# system-controller.net
KiCad netlist of a schematic drawn in EAGLE
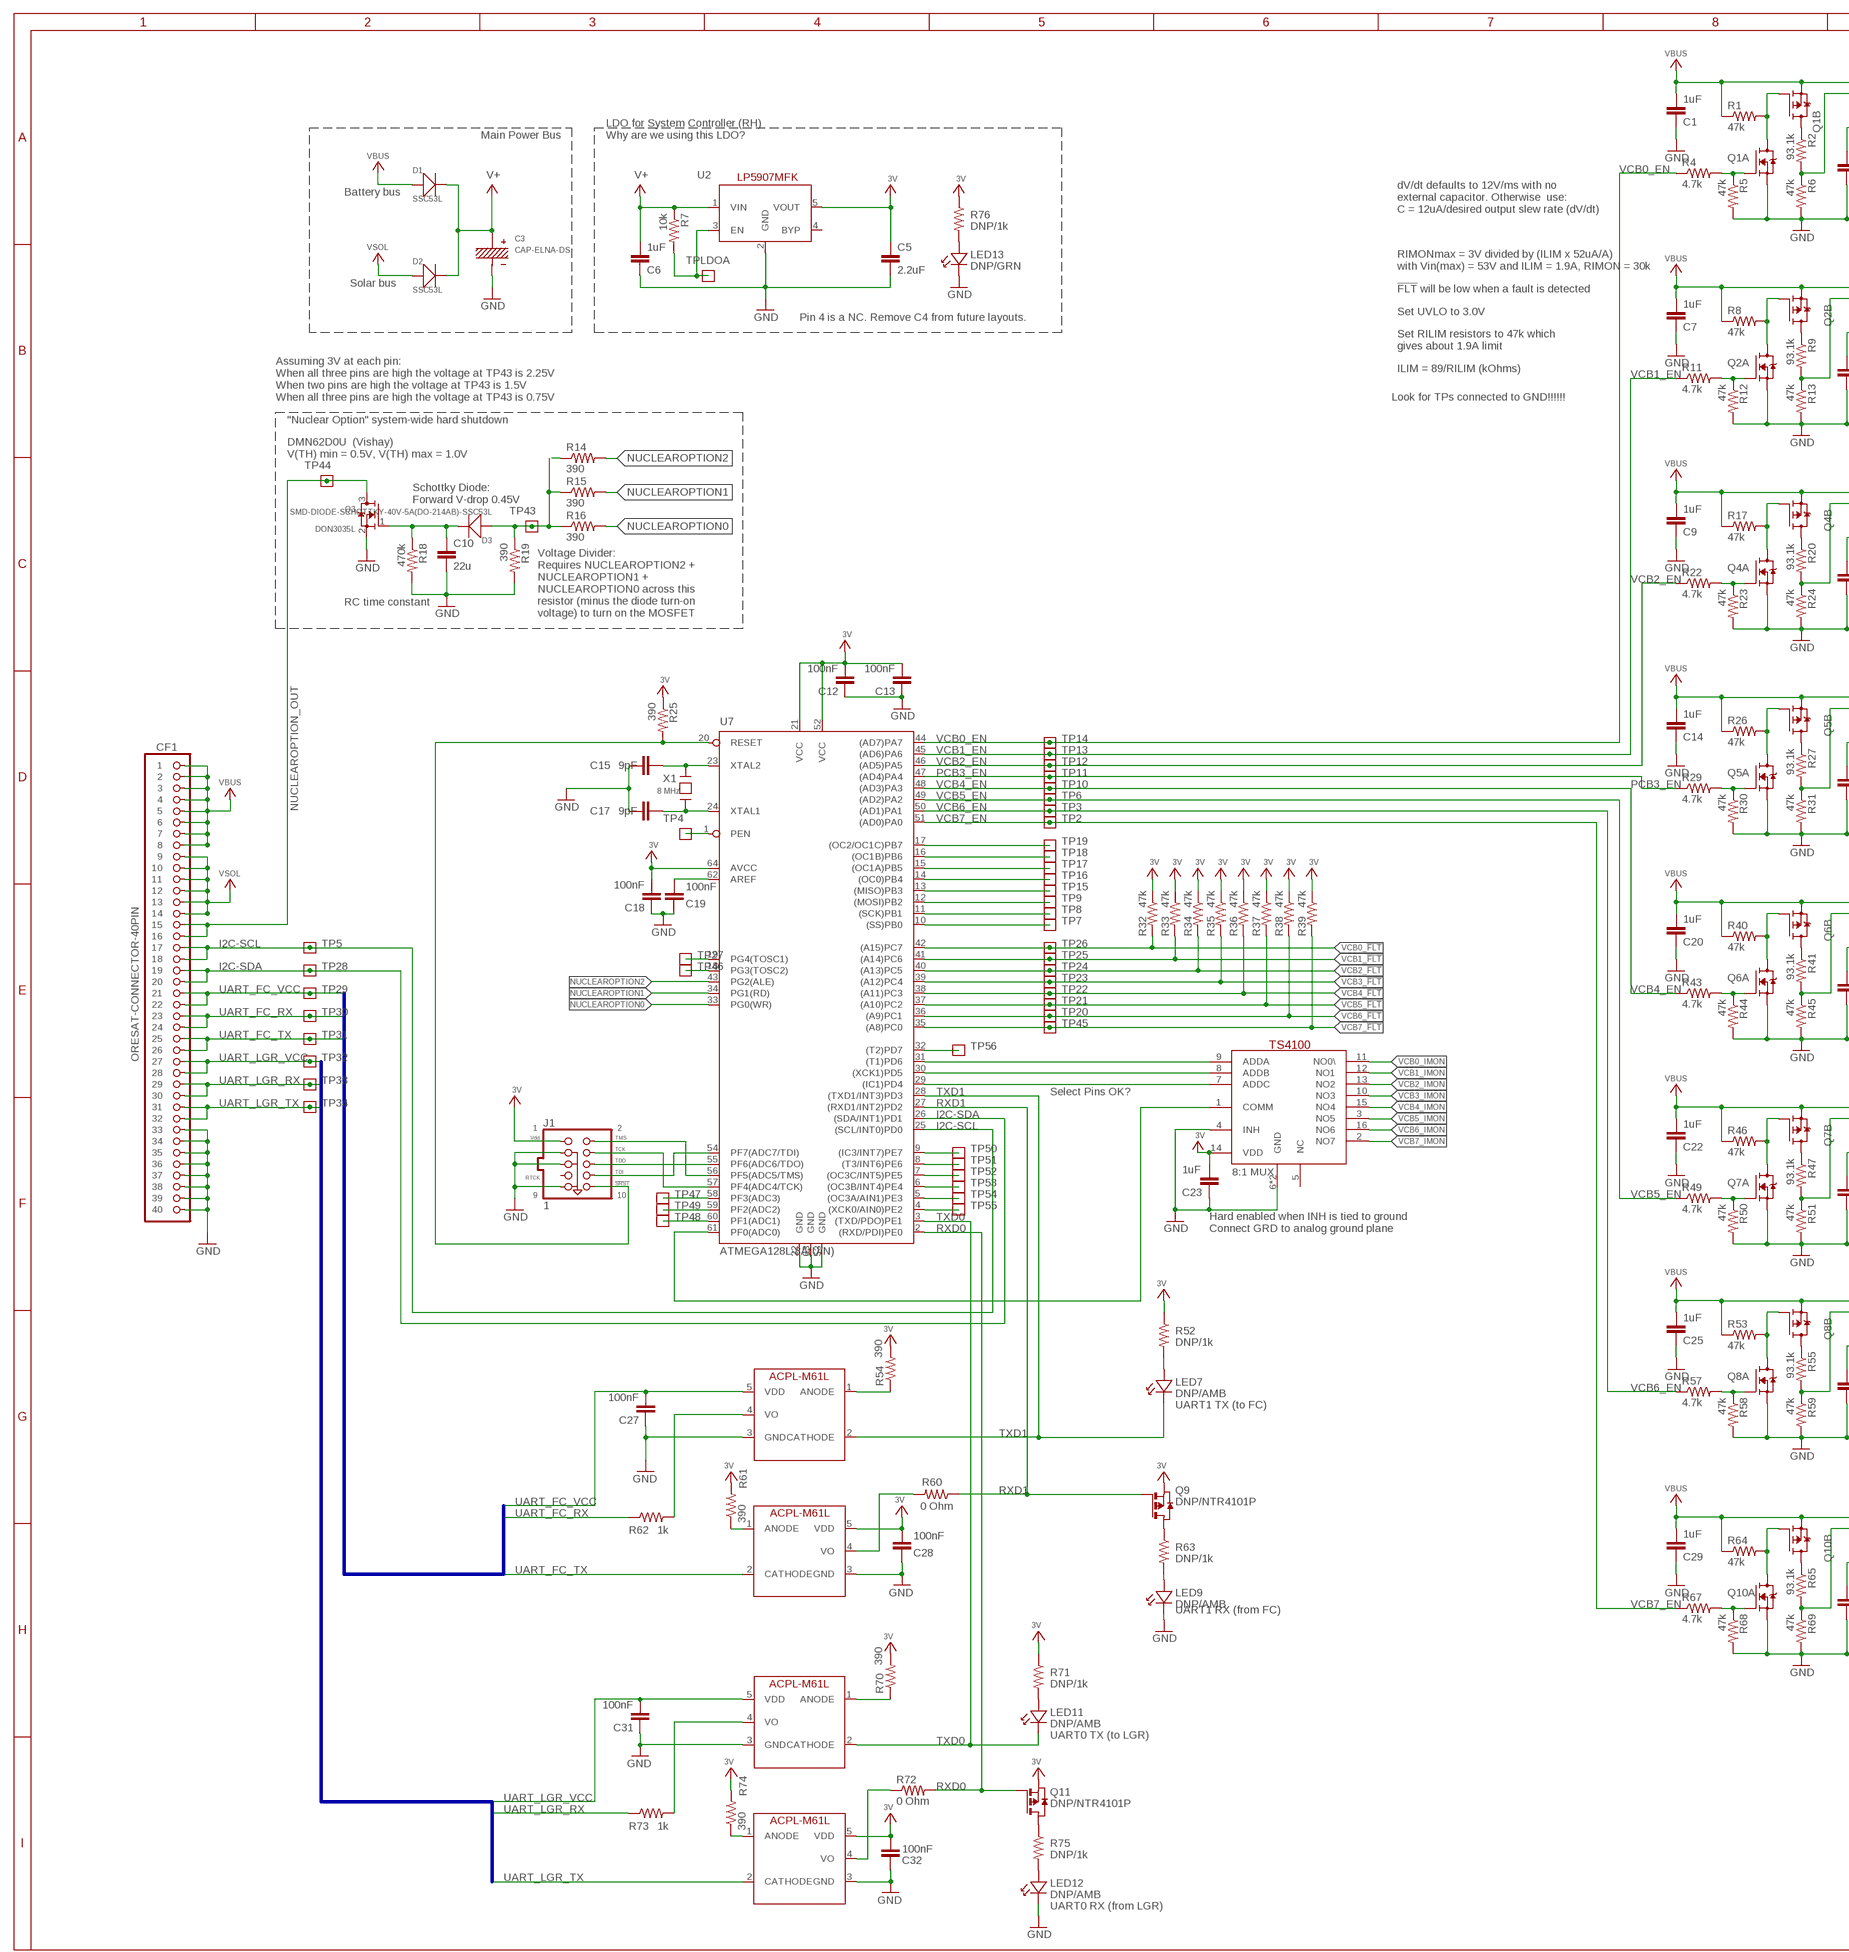
[diagram p0: schematic, sheet 1, part 1 of 2]
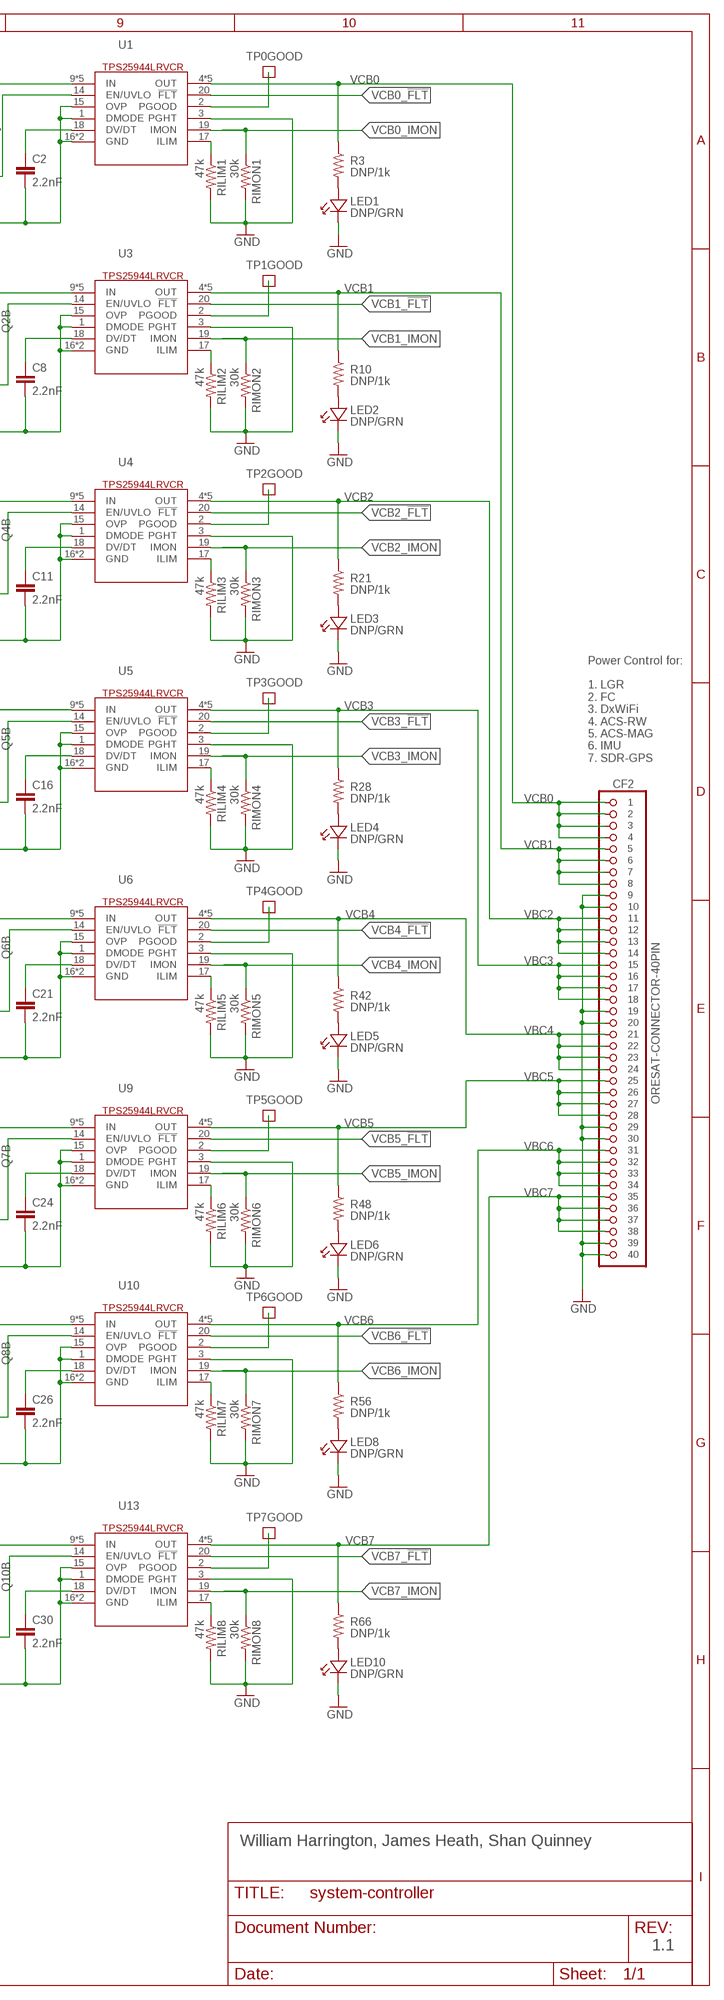
[diagram p1: schematic, sheet 1, part 2 of 2]

(export (version "E")
  (design (tool "Eeschema 10.0.6"))
  (components
    (comp (ref "C1")
      (value "1uF")
      (footprint "eagle-import:.0603-B-NOSILK")
      (fields (field (name "MPN") "CL10B105KP8NNNC"))
      (libsource (lib "eagle-import") (part "C-EU0603-B-NOSILK"))
    )
    (comp (ref "C2")
      (value "2.2nF")
      (footprint "eagle-import:.0603-B-NOSILK")
      (fields (field (name "MPN") "CL10C222GA8NNNC"))
      (libsource (lib "eagle-import") (part "C-EU0603-B-NOSILK"))
    )
    (comp (ref "C3")
      (value "CAP-ELNA-DS")
      (footprint "eagle-import:CAP-ELNA-DS-SERIES")
      (fields (field (name "MPN") "DSK-3R3H224U-HL"))
      (libsource (lib "eagle-import") (part "CAP-ELNA-DS"))
    )
    (comp (ref "C5")
      (value "2.2uF")
      (footprint "eagle-import:.0603-B-NOSILK")
      (fields (field (name "MPN") "CL10A225KQ8NNNC"))
      (libsource (lib "eagle-import") (part "C-EU0603-B-NOSILK"))
    )
    (comp (ref "C6")
      (value "1uF")
      (footprint "eagle-import:.0603-B-NOSILK")
      (fields (field (name "MPN") "CL10B105KP8NNNC"))
      (libsource (lib "eagle-import") (part "C-EU0603-B-NOSILK"))
    )
    (comp (ref "C7")
      (value "1uF")
      (footprint "eagle-import:.0603-B-NOSILK")
      (fields (field (name "MPN") "CL10B105KP8NNNC"))
      (libsource (lib "eagle-import") (part "C-EU0603-B-NOSILK"))
    )
    (comp (ref "C8")
      (value "2.2nF")
      (footprint "eagle-import:.0603-B-NOSILK")
      (fields (field (name "MPN") "CL10C222GA8NNNC"))
      (libsource (lib "eagle-import") (part "C-EU0603-B-NOSILK"))
    )
    (comp (ref "C9")
      (value "1uF")
      (footprint "eagle-import:.0603-B-NOSILK")
      (fields (field (name "MPN") "CL10B105KP8NNNC"))
      (libsource (lib "eagle-import") (part "C-EU0603-B-NOSILK"))
    )
    (comp (ref "C10")
      (value "22u")
      (footprint "eagle-import:.0603-B-NOSILK")
      (fields (field (name "MPN") "C0603C103J5RACTU"))
      (libsource (lib "eagle-import") (part "C-EU0603-B-NOSILK"))
    )
    (comp (ref "C11")
      (value "2.2nF")
      (footprint "eagle-import:.0603-B-NOSILK")
      (fields (field (name "MPN") "CL10C222GA8NNNC"))
      (libsource (lib "eagle-import") (part "C-EU0603-B-NOSILK"))
    )
    (comp (ref "C12")
      (value "100nF")
      (footprint "eagle-import:.0603-B-NOSILK")
      (fields (field (name "MPN") "C0603C104J4RACTU"))
      (libsource (lib "eagle-import") (part "C-EU0603-B-NOSILK"))
    )
    (comp (ref "C13")
      (value "100nF")
      (footprint "eagle-import:.0603-B-NOSILK")
      (fields (field (name "MPN") "C0603C104J4RACTU"))
      (libsource (lib "eagle-import") (part "C-EU0603-B-NOSILK"))
    )
    (comp (ref "C14")
      (value "1uF")
      (footprint "eagle-import:.0603-B-NOSILK")
      (fields (field (name "MPN") "CL10B105KP8NNNC"))
      (libsource (lib "eagle-import") (part "C-EU0603-B-NOSILK"))
    )
    (comp (ref "C15")
      (value "9pF")
      (footprint "eagle-import:.0603-B-NOSILK")
      (fields (field (name "MPN") "CBR02C909B5GAC"))
      (libsource (lib "eagle-import") (part "C-EU0603-B-NOSILK"))
    )
    (comp (ref "C16")
      (value "2.2nF")
      (footprint "eagle-import:.0603-B-NOSILK")
      (fields (field (name "MPN") "CL10C222GA8NNNC"))
      (libsource (lib "eagle-import") (part "C-EU0603-B-NOSILK"))
    )
    (comp (ref "C17")
      (value "9pF")
      (footprint "eagle-import:.0603-B-NOSILK")
      (fields (field (name "MPN") "CBR02C909B5GAC"))
      (libsource (lib "eagle-import") (part "C-EU0603-B-NOSILK"))
    )
    (comp (ref "C18")
      (value "100nF")
      (footprint "eagle-import:.0603-B-NOSILK")
      (fields (field (name "MPN") "C0603C104J4RACTU"))
      (libsource (lib "eagle-import") (part "C-EU0603-B-NOSILK"))
    )
    (comp (ref "C19")
      (value "100nF")
      (footprint "eagle-import:.0603-B-NOSILK")
      (fields (field (name "MPN") "C0603C104J4RACTU"))
      (libsource (lib "eagle-import") (part "C-EU0603-B-NOSILK"))
    )
    (comp (ref "C20")
      (value "1uF")
      (footprint "eagle-import:.0603-B-NOSILK")
      (fields (field (name "MPN") "CL10B105KP8NNNC"))
      (libsource (lib "eagle-import") (part "C-EU0603-B-NOSILK"))
    )
    (comp (ref "C21")
      (value "2.2nF")
      (footprint "eagle-import:.0603-B-NOSILK")
      (fields (field (name "MPN") "CL10C222GA8NNNC"))
      (libsource (lib "eagle-import") (part "C-EU0603-B-NOSILK"))
    )
    (comp (ref "C22")
      (value "1uF")
      (footprint "eagle-import:.0603-B-NOSILK")
      (fields (field (name "MPN") "CL10B105KP8NNNC"))
      (libsource (lib "eagle-import") (part "C-EU0603-B-NOSILK"))
    )
    (comp (ref "C23")
      (value "1uF")
      (footprint "eagle-import:.0603-B-NOSILK")
      (fields (field (name "MPN") "CL10B105KP8NNNC"))
      (libsource (lib "eagle-import") (part "C-EU0603-B-NOSILK"))
    )
    (comp (ref "C24")
      (value "2.2nF")
      (footprint "eagle-import:.0603-B-NOSILK")
      (fields (field (name "MPN") "CL10C222GA8NNNC"))
      (libsource (lib "eagle-import") (part "C-EU0603-B-NOSILK"))
    )
    (comp (ref "C25")
      (value "1uF")
      (footprint "eagle-import:.0603-B-NOSILK")
      (fields (field (name "MPN") "CL10B105KP8NNNC"))
      (libsource (lib "eagle-import") (part "C-EU0603-B-NOSILK"))
    )
    (comp (ref "C26")
      (value "2.2nF")
      (footprint "eagle-import:.0603-B-NOSILK")
      (fields (field (name "MPN") "CL10C222GA8NNNC"))
      (libsource (lib "eagle-import") (part "C-EU0603-B-NOSILK"))
    )
    (comp (ref "C27")
      (value "100nF")
      (footprint "eagle-import:.0603-B-NOSILK")
      (fields (field (name "MPN") "C0603C104J4RACTU"))
      (libsource (lib "eagle-import") (part "C-EU0603-B-NOSILK"))
    )
    (comp (ref "C28")
      (value "100nF")
      (footprint "eagle-import:.0603-B-NOSILK")
      (fields (field (name "MPN") "C0603C104J4RACTU"))
      (libsource (lib "eagle-import") (part "C-EU0603-B-NOSILK"))
    )
    (comp (ref "C29")
      (value "1uF")
      (footprint "eagle-import:.0603-B-NOSILK")
      (fields (field (name "MPN") "CL10B105KP8NNNC"))
      (libsource (lib "eagle-import") (part "C-EU0603-B-NOSILK"))
    )
    (comp (ref "C30")
      (value "2.2nF")
      (footprint "eagle-import:.0603-B-NOSILK")
      (fields (field (name "MPN") "CL10C222GA8NNNC"))
      (libsource (lib "eagle-import") (part "C-EU0603-B-NOSILK"))
    )
    (comp (ref "C31")
      (value "100nF")
      (footprint "eagle-import:.0603-B-NOSILK")
      (fields (field (name "MPN") "GRM155R71C104JA88D"))
      (libsource (lib "eagle-import") (part "C-EU0603-B-NOSILK"))
    )
    (comp (ref "C32")
      (value "100nF")
      (footprint "eagle-import:.0603-B-NOSILK")
      (fields (field (name "MPN") "GRM155R71C104JA88D"))
      (libsource (lib "eagle-import") (part "C-EU0603-B-NOSILK"))
    )
    (comp (ref "CF1")
      (value "ORESAT-CONNECTOR-40PIN")
      (footprint "eagle-import:HARWIN-ARCHER-M50-3202045")
      (fields (field (name "MPN") "M50-3202045"))
      (libsource (lib "eagle-import") (part "ORESAT-CONNECTOR-40PIN"))
    )
    (comp (ref "CF2")
      (value "ORESAT-CONNECTOR-40PIN")
      (footprint "eagle-import:HARWIN-ARCHER-M50-3202045")
      (fields (field (name "MPN") "M50-3202045"))
      (libsource (lib "eagle-import") (part "ORESAT-CONNECTOR-40PIN"))
    )
    (comp (ref "D1")
      (value "SSC53L")
      (footprint "eagle-import:DO-214AB")
      (fields (field (name "MPN") "SSC53L-E3/57T"))
      (libsource (lib "eagle-import") (part "SMD-DIODE-SCHOTTKY-40V-5A(DO-214AB)-SSC53L"))
    )
    (comp (ref "D2")
      (value "SSC53L")
      (footprint "eagle-import:DO-214AB")
      (fields (field (name "MPN") "SSC53L-E3/57T"))
      (libsource (lib "eagle-import") (part "SMD-DIODE-SCHOTTKY-40V-5A(DO-214AB)-SSC53L"))
    )
    (comp (ref "D3")
      (value "SMD-DIODE-SCHOTTKY-40V-5A(DO-214AB)-SSC53L")
      (footprint "eagle-import:DO-214AB")
      (fields (field (name "MPN") "SSC53L-E3/57T"))
      (libsource (lib "eagle-import") (part "SMD-DIODE-SCHOTTKY-40V-5A(DO-214AB)-SSC53L"))
    )
    (comp (ref "J1")
      (value "1")
      (footprint "eagle-import:PINHEADER-2X5-0.05+POL+SILK")
      (fields (field (name "MPN") "3220-10-0100-00"))
      (libsource (lib "eagle-import") (part "JTAG_ARM-10-50MIL"))
    )
    (comp (ref "LED1")
      (value "DNP/GRN")
      (footprint "eagle-import:LED-0603")
      (fields (field (name "MPN") "150060GS75000"))
      (libsource (lib "eagle-import") (part "LED-0603"))
    )
    (comp (ref "LED2")
      (value "DNP/GRN")
      (footprint "eagle-import:LED-0603")
      (fields (field (name "MPN") "150060GS75000"))
      (libsource (lib "eagle-import") (part "LED-0603"))
    )
    (comp (ref "LED3")
      (value "DNP/GRN")
      (footprint "eagle-import:LED-0603")
      (fields (field (name "MPN") "150060GS75000"))
      (libsource (lib "eagle-import") (part "LED-0603"))
    )
    (comp (ref "LED4")
      (value "DNP/GRN")
      (footprint "eagle-import:LED-0603")
      (fields (field (name "MPN") "150060GS75000"))
      (libsource (lib "eagle-import") (part "LED-0603"))
    )
    (comp (ref "LED5")
      (value "DNP/GRN")
      (footprint "eagle-import:LED-0603")
      (fields (field (name "MPN") "150060GS75000"))
      (libsource (lib "eagle-import") (part "LED-0603"))
    )
    (comp (ref "LED6")
      (value "DNP/GRN")
      (footprint "eagle-import:LED-0603")
      (fields (field (name "MPN") "150060GS75000"))
      (libsource (lib "eagle-import") (part "LED-0603"))
    )
    (comp (ref "LED7")
      (value "DNP/AMB")
      (footprint "eagle-import:LED-0603")
      (fields (field (name "MPN") "LA L296-Q2R2-1-Z"))
      (libsource (lib "eagle-import") (part "LED-0603"))
    )
    (comp (ref "LED8")
      (value "DNP/GRN")
      (footprint "eagle-import:LED-0603")
      (fields (field (name "MPN") "150060GS75000"))
      (libsource (lib "eagle-import") (part "LED-0603"))
    )
    (comp (ref "LED9")
      (value "DNP/AMB")
      (footprint "eagle-import:LED-0603")
      (fields (field (name "MPN") "LA L296-Q2R2-1-Z"))
      (libsource (lib "eagle-import") (part "LED-0603"))
    )
    (comp (ref "LED10")
      (value "DNP/GRN")
      (footprint "eagle-import:LED-0603")
      (fields (field (name "MPN") "150060GS75000"))
      (libsource (lib "eagle-import") (part "LED-0603"))
    )
    (comp (ref "LED11")
      (value "DNP/AMB")
      (footprint "eagle-import:LED-0603")
      (fields (field (name "MPN") "LA L296-Q2R2-1-Z"))
      (libsource (lib "eagle-import") (part "LED-0603"))
    )
    (comp (ref "LED12")
      (value "DNP/AMB")
      (footprint "eagle-import:LED-0603")
      (fields (field (name "MPN") "LA L296-Q2R2-1-Z"))
      (libsource (lib "eagle-import") (part "LED-0603"))
    )
    (comp (ref "LED13")
      (value "DNP/GRN")
      (footprint "eagle-import:LED-0603")
      (fields (field (name "MPN") "150060GS75000"))
      (libsource (lib "eagle-import") (part "LED-0603"))
    )
    (comp (ref "Q1")
      (value "MOSFET-P-N-PAIR")
      (footprint "eagle-import:SOT23-6")
      (fields
        (field (name "MPN") "DMG6601LVT-7")
        (field (name "DIST") "digikey")
        (field (name "DPN") "DMG6601LVT-7DICT-ND")
        (field (name "MFN") "Diodes Incorporated")
      )
      (libsource (lib "eagle-import") (part "MOSFET-P-N-PAIR"))
    )
    (comp (ref "Q2")
      (value "MOSFET-P-N-PAIR")
      (footprint "eagle-import:SOT23-6")
      (fields
        (field (name "MPN") "DMG6601LVT-7")
        (field (name "DIST") "digikey")
        (field (name "DPN") "DMG6601LVT-7DICT-ND")
        (field (name "MFN") "Diodes Incorporated")
      )
      (libsource (lib "eagle-import") (part "MOSFET-P-N-PAIR"))
    )
    (comp (ref "Q3")
      (value "DON3035L")
      (footprint "eagle-import:SOT23")
      (fields (field (name "MPN") "DMN62D0U-13"))
      (libsource (lib "eagle-import") (part "MOSFET-NREFLOW"))
    )
    (comp (ref "Q4")
      (value "MOSFET-P-N-PAIR")
      (footprint "eagle-import:SOT23-6")
      (fields
        (field (name "MPN") "DMG6601LVT-7")
        (field (name "DIST") "digikey")
        (field (name "DPN") "DMG6601LVT-7DICT-ND")
        (field (name "MFN") "Diodes Incorporated")
      )
      (libsource (lib "eagle-import") (part "MOSFET-P-N-PAIR"))
    )
    (comp (ref "Q5")
      (value "MOSFET-P-N-PAIR")
      (footprint "eagle-import:SOT23-6")
      (fields
        (field (name "MPN") "DMG6601LVT-7")
        (field (name "DIST") "digikey")
        (field (name "DPN") "DMG6601LVT-7DICT-ND")
        (field (name "MFN") "Diodes Incorporated")
      )
      (libsource (lib "eagle-import") (part "MOSFET-P-N-PAIR"))
    )
    (comp (ref "Q6")
      (value "MOSFET-P-N-PAIR")
      (footprint "eagle-import:SOT23-6")
      (fields
        (field (name "DIST") "digikey")
        (field (name "DPN") "DMG6601LVT-7DICT-ND")
        (field (name "MFN") "Diodes Incorporated")
        (field (name "MPN") "DMG6601LVT-7")
      )
      (libsource (lib "eagle-import") (part "MOSFET-P-N-PAIR"))
    )
    (comp (ref "Q7")
      (value "MOSFET-P-N-PAIR")
      (footprint "eagle-import:SOT23-6")
      (fields
        (field (name "DIST") "digikey")
        (field (name "DPN") "DMG6601LVT-7DICT-ND")
        (field (name "MFN") "Diodes Incorporated")
        (field (name "MPN") "DMG6601LVT-7")
      )
      (libsource (lib "eagle-import") (part "MOSFET-P-N-PAIR"))
    )
    (comp (ref "Q8")
      (value "MOSFET-P-N-PAIR")
      (footprint "eagle-import:SOT23-6")
      (fields
        (field (name "DIST") "digikey")
        (field (name "DPN") "DMG6601LVT-7DICT-ND")
        (field (name "MFN") "Diodes Incorporated")
        (field (name "MPN") "DMG6601LVT-7")
      )
      (libsource (lib "eagle-import") (part "MOSFET-P-N-PAIR"))
    )
    (comp (ref "Q9")
      (value "DNP/NTR4101P")
      (footprint "eagle-import:SOT23")
      (fields (field (name "MPN") "NTR4101PT1H"))
      (libsource (lib "eagle-import") (part "NTR4101P"))
    )
    (comp (ref "Q10")
      (value "MOSFET-P-N-PAIR")
      (footprint "eagle-import:SOT23-6")
      (fields
        (field (name "DIST") "digikey")
        (field (name "DPN") "DMG6601LVT-7DICT-ND")
        (field (name "MFN") "Diodes Incorporated")
        (field (name "MPN") "DMG6601LVT-7")
      )
      (libsource (lib "eagle-import") (part "MOSFET-P-N-PAIR"))
    )
    (comp (ref "Q11")
      (value "DNP/NTR4101P")
      (footprint "eagle-import:SOT23")
      (fields (field (name "MPN") "NTR4101PT1H"))
      (libsource (lib "eagle-import") (part "NTR4101P"))
    )
    (comp (ref "R1")
      (value "47k")
      (footprint "eagle-import:.0603-B-NOSILK")
      (fields (field (name "MPN") "RC1608F473CS"))
      (libsource (lib "eagle-import") (part "R-US_0603-B-NOSILK"))
    )
    (comp (ref "R2")
      (value "93.1k")
      (footprint "eagle-import:.0603-B-NOSILK")
      (fields (field (name "MPN") "RC1608F9312CS"))
      (libsource (lib "eagle-import") (part "R-US_0603-B-NOSILK"))
    )
    (comp (ref "R3")
      (value "DNP/1k")
      (footprint "eagle-import:.0603-B-NOSILK")
      (fields (field (name "MPN") "RC1608F102CS"))
      (libsource (lib "eagle-import") (part "R-US_0603-B-NOSILK"))
    )
    (comp (ref "R4")
      (value "4.7k")
      (footprint "eagle-import:.0603-B-NOSILK")
      (fields (field (name "MPN") "RC1608F472CS"))
      (libsource (lib "eagle-import") (part "R-US_0603-B-NOSILK"))
    )
    (comp (ref "R5")
      (value "47k")
      (footprint "eagle-import:.0603-B-NOSILK")
      (fields (field (name "MPN") "RC1608F473CS"))
      (libsource (lib "eagle-import") (part "R-US_0603-B-NOSILK"))
    )
    (comp (ref "R6")
      (value "47k")
      (footprint "eagle-import:.0603-B-NOSILK")
      (fields (field (name "MPN") "RC1608F473CS"))
      (libsource (lib "eagle-import") (part "R-US_0603-B-NOSILK"))
    )
    (comp (ref "R7")
      (value "10k")
      (footprint "eagle-import:.0603-B-NOSILK")
      (fields (field (name "MPN") "RC1608F103CS"))
      (libsource (lib "eagle-import") (part "R-US_0603-B-NOSILK"))
    )
    (comp (ref "R8")
      (value "47k")
      (footprint "eagle-import:.0603-B-NOSILK")
      (fields (field (name "MPN") "RC1608F473CS"))
      (libsource (lib "eagle-import") (part "R-US_0603-B-NOSILK"))
    )
    (comp (ref "R9")
      (value "93.1k")
      (footprint "eagle-import:.0603-B-NOSILK")
      (fields (field (name "MPN") "RC1608F9312CS"))
      (libsource (lib "eagle-import") (part "R-US_0603-B-NOSILK"))
    )
    (comp (ref "R10")
      (value "DNP/1k")
      (footprint "eagle-import:.0603-B-NOSILK")
      (fields (field (name "MPN") "RC1608F102CS"))
      (libsource (lib "eagle-import") (part "R-US_0603-B-NOSILK"))
    )
    (comp (ref "R11")
      (value "4.7k")
      (footprint "eagle-import:.0603-B-NOSILK")
      (fields (field (name "MPN") "RC1608F472CS"))
      (libsource (lib "eagle-import") (part "R-US_0603-B-NOSILK"))
    )
    (comp (ref "R12")
      (value "47k")
      (footprint "eagle-import:.0603-B-NOSILK")
      (fields (field (name "MPN") "RC1608F473CS"))
      (libsource (lib "eagle-import") (part "R-US_0603-B-NOSILK"))
    )
    (comp (ref "R13")
      (value "47k")
      (footprint "eagle-import:.0603-B-NOSILK")
      (fields (field (name "MPN") "RC1608F473CS"))
      (libsource (lib "eagle-import") (part "R-US_0603-B-NOSILK"))
    )
    (comp (ref "R14")
      (value "390")
      (footprint "eagle-import:.0603-B-NOSILK")
      (fields (field (name "MPN") "4-1676481-5"))
      (libsource (lib "eagle-import") (part "R-US_0603-B-NOSILK"))
    )
    (comp (ref "R15")
      (value "390")
      (footprint "eagle-import:.0603-B-NOSILK")
      (fields (field (name "MPN") "4-1676481-5"))
      (libsource (lib "eagle-import") (part "R-US_0603-B-NOSILK"))
    )
    (comp (ref "R16")
      (value "390")
      (footprint "eagle-import:.0603-B-NOSILK")
      (fields (field (name "MPN") "4-1676481-5"))
      (libsource (lib "eagle-import") (part "R-US_0603-B-NOSILK"))
    )
    (comp (ref "R17")
      (value "47k")
      (footprint "eagle-import:.0603-B-NOSILK")
      (fields (field (name "MPN") "RC1608F473CS"))
      (libsource (lib "eagle-import") (part "R-US_0603-B-NOSILK"))
    )
    (comp (ref "R18")
      (value "470k")
      (footprint "eagle-import:.0603-B-NOSILK")
      (fields (field (name "MPN") "RC1608F474CS"))
      (libsource (lib "eagle-import") (part "R-US_0603-B-NOSILK"))
    )
    (comp (ref "R19")
      (value "390")
      (footprint "eagle-import:.0603-B-NOSILK")
      (fields (field (name "MPN") "4-1676481-5"))
      (libsource (lib "eagle-import") (part "R-US_0603-B-NOSILK"))
    )
    (comp (ref "R20")
      (value "93.1k")
      (footprint "eagle-import:.0603-B-NOSILK")
      (fields (field (name "MPN") "RC1608F9312CS"))
      (libsource (lib "eagle-import") (part "R-US_0603-B-NOSILK"))
    )
    (comp (ref "R21")
      (value "DNP/1k")
      (footprint "eagle-import:.0603-B-NOSILK")
      (fields (field (name "MPN") "RC1608F102CS"))
      (libsource (lib "eagle-import") (part "R-US_0603-B-NOSILK"))
    )
    (comp (ref "R22")
      (value "4.7k")
      (footprint "eagle-import:.0603-B-NOSILK")
      (fields (field (name "MPN") "RC1608F472CS"))
      (libsource (lib "eagle-import") (part "R-US_0603-B-NOSILK"))
    )
    (comp (ref "R23")
      (value "47k")
      (footprint "eagle-import:.0603-B-NOSILK")
      (fields (field (name "MPN") "RC1608F473CS"))
      (libsource (lib "eagle-import") (part "R-US_0603-B-NOSILK"))
    )
    (comp (ref "R24")
      (value "47k")
      (footprint "eagle-import:.0603-B-NOSILK")
      (fields (field (name "MPN") "RC1608F473CS"))
      (libsource (lib "eagle-import") (part "R-US_0603-B-NOSILK"))
    )
    (comp (ref "R25")
      (value "390")
      (footprint "eagle-import:.0603-B-NOSILK")
      (fields (field (name "MPN") "4-1676481-5"))
      (libsource (lib "eagle-import") (part "R-US_0603-B-NOSILK"))
    )
    (comp (ref "R26")
      (value "47k")
      (footprint "eagle-import:.0603-B-NOSILK")
      (fields (field (name "MPN") "RC1608F473CS"))
      (libsource (lib "eagle-import") (part "R-US_0603-B-NOSILK"))
    )
    (comp (ref "R27")
      (value "93.1k")
      (footprint "eagle-import:.0603-B-NOSILK")
      (fields (field (name "MPN") "RC1608F9312CS"))
      (libsource (lib "eagle-import") (part "R-US_0603-B-NOSILK"))
    )
    (comp (ref "R28")
      (value "DNP/1k")
      (footprint "eagle-import:.0603-B-NOSILK")
      (fields (field (name "MPN") "RC1608F102CS"))
      (libsource (lib "eagle-import") (part "R-US_0603-B-NOSILK"))
    )
    (comp (ref "R29")
      (value "4.7k")
      (footprint "eagle-import:.0603-B-NOSILK")
      (fields (field (name "MPN") "RC1608F472CS"))
      (libsource (lib "eagle-import") (part "R-US_0603-B-NOSILK"))
    )
    (comp (ref "R30")
      (value "47k")
      (footprint "eagle-import:.0603-B-NOSILK")
      (fields (field (name "MPN") "RC1608F473CS"))
      (libsource (lib "eagle-import") (part "R-US_0603-B-NOSILK"))
    )
    (comp (ref "R31")
      (value "47k")
      (footprint "eagle-import:.0603-B-NOSILK")
      (fields (field (name "MPN") "RC1608F473CS"))
      (libsource (lib "eagle-import") (part "R-US_0603-B-NOSILK"))
    )
    (comp (ref "R32")
      (value "47k")
      (footprint "eagle-import:.0603-B-NOSILK")
      (fields (field (name "MPN") "RC1608F473CS"))
      (libsource (lib "eagle-import") (part "R-US_0603-B-NOSILK"))
    )
    (comp (ref "R33")
      (value "47k")
      (footprint "eagle-import:.0603-B-NOSILK")
      (fields (field (name "MPN") "RC1608F473CS"))
      (libsource (lib "eagle-import") (part "R-US_0603-B-NOSILK"))
    )
    (comp (ref "R34")
      (value "47k")
      (footprint "eagle-import:.0603-B-NOSILK")
      (fields (field (name "MPN") "RC1608F473CS"))
      (libsource (lib "eagle-import") (part "R-US_0603-B-NOSILK"))
    )
    (comp (ref "R35")
      (value "47k")
      (footprint "eagle-import:.0603-B-NOSILK")
      (fields (field (name "MPN") "RC1608F473CS"))
      (libsource (lib "eagle-import") (part "R-US_0603-B-NOSILK"))
    )
    (comp (ref "R36")
      (value "47k")
      (footprint "eagle-import:.0603-B-NOSILK")
      (fields (field (name "MPN") "RC1608F473CS"))
      (libsource (lib "eagle-import") (part "R-US_0603-B-NOSILK"))
    )
    (comp (ref "R37")
      (value "47k")
      (footprint "eagle-import:.0603-B-NOSILK")
      (fields (field (name "MPN") "RC1608F473CS"))
      (libsource (lib "eagle-import") (part "R-US_0603-B-NOSILK"))
    )
    (comp (ref "R38")
      (value "47k")
      (footprint "eagle-import:.0603-B-NOSILK")
      (fields (field (name "MPN") "RC1608F473CS"))
      (libsource (lib "eagle-import") (part "R-US_0603-B-NOSILK"))
    )
    (comp (ref "R39")
      (value "47k")
      (footprint "eagle-import:.0603-B-NOSILK")
      (fields (field (name "MPN") "RC1608F473CS"))
      (libsource (lib "eagle-import") (part "R-US_0603-B-NOSILK"))
    )
    (comp (ref "R40")
      (value "47k")
      (footprint "eagle-import:.0603-B-NOSILK")
      (fields (field (name "MPN") "RC1608F473CS"))
      (libsource (lib "eagle-import") (part "R-US_0603-B-NOSILK"))
    )
    (comp (ref "R41")
      (value "93.1k")
      (footprint "eagle-import:.0603-B-NOSILK")
      (fields (field (name "MPN") "RC1608F9312CS"))
      (libsource (lib "eagle-import") (part "R-US_0603-B-NOSILK"))
    )
    (comp (ref "R42")
      (value "DNP/1k")
      (footprint "eagle-import:.0603-B-NOSILK")
      (fields (field (name "MPN") "RC1608F102CS"))
      (libsource (lib "eagle-import") (part "R-US_0603-B-NOSILK"))
    )
    (comp (ref "R43")
      (value "4.7k")
      (footprint "eagle-import:.0603-B-NOSILK")
      (fields (field (name "MPN") "RC1608F472CS"))
      (libsource (lib "eagle-import") (part "R-US_0603-B-NOSILK"))
    )
    (comp (ref "R44")
      (value "47k")
      (footprint "eagle-import:.0603-B-NOSILK")
      (fields (field (name "MPN") "RC1608F473CS"))
      (libsource (lib "eagle-import") (part "R-US_0603-B-NOSILK"))
    )
    (comp (ref "R45")
      (value "47k")
      (footprint "eagle-import:.0603-B-NOSILK")
      (fields (field (name "MPN") "RC1608F473CS"))
      (libsource (lib "eagle-import") (part "R-US_0603-B-NOSILK"))
    )
    (comp (ref "R46")
      (value "47k")
      (footprint "eagle-import:.0603-B-NOSILK")
      (fields (field (name "MPN") "RC1608F473CS"))
      (libsource (lib "eagle-import") (part "R-US_0603-B-NOSILK"))
    )
    (comp (ref "R47")
      (value "93.1k")
      (footprint "eagle-import:.0603-B-NOSILK")
      (fields (field (name "MPN") "RC1608F9312CS"))
      (libsource (lib "eagle-import") (part "R-US_0603-B-NOSILK"))
    )
    (comp (ref "R48")
      (value "DNP/1k")
      (footprint "eagle-import:.0603-B-NOSILK")
      (fields (field (name "MPN") "RC1608F102CS"))
      (libsource (lib "eagle-import") (part "R-US_0603-B-NOSILK"))
    )
    (comp (ref "R49")
      (value "4.7k")
      (footprint "eagle-import:.0603-B-NOSILK")
      (fields (field (name "MPN") "RC1608F472CS"))
      (libsource (lib "eagle-import") (part "R-US_0603-B-NOSILK"))
    )
    (comp (ref "R50")
      (value "47k")
      (footprint "eagle-import:.0603-B-NOSILK")
      (fields (field (name "MPN") "RC1608F473CS"))
      (libsource (lib "eagle-import") (part "R-US_0603-B-NOSILK"))
    )
    (comp (ref "R51")
      (value "47k")
      (footprint "eagle-import:.0603-B-NOSILK")
      (fields (field (name "MPN") "RC1608F473CS"))
      (libsource (lib "eagle-import") (part "R-US_0603-B-NOSILK"))
    )
    (comp (ref "R52")
      (value "DNP/1k")
      (footprint "eagle-import:.0603-B-NOSILK")
      (fields (field (name "MPN") "RC1608F102CS"))
      (libsource (lib "eagle-import") (part "R-US_0603-B-NOSILK"))
    )
    (comp (ref "R53")
      (value "47k")
      (footprint "eagle-import:.0603-B-NOSILK")
      (fields (field (name "MPN") "RC1608F473CS"))
      (libsource (lib "eagle-import") (part "R-US_0603-B-NOSILK"))
    )
    (comp (ref "R54")
      (value "390")
      (footprint "eagle-import:.0603-B-NOSILK")
      (fields (field (name "MPN") "4-1676481-5"))
      (libsource (lib "eagle-import") (part "R-US_0603-B-NOSILK"))
    )
    (comp (ref "R55")
      (value "93.1k")
      (footprint "eagle-import:.0603-B-NOSILK")
      (fields (field (name "MPN") "RC1608F9312CS"))
      (libsource (lib "eagle-import") (part "R-US_0603-B-NOSILK"))
    )
    (comp (ref "R56")
      (value "DNP/1k")
      (footprint "eagle-import:.0603-B-NOSILK")
      (fields (field (name "MPN") "RC1608F102CS"))
      (libsource (lib "eagle-import") (part "R-US_0603-B-NOSILK"))
    )
    (comp (ref "R57")
      (value "4.7k")
      (footprint "eagle-import:.0603-B-NOSILK")
      (fields (field (name "MPN") "RC1608F472CS"))
      (libsource (lib "eagle-import") (part "R-US_0603-B-NOSILK"))
    )
    (comp (ref "R58")
      (value "47k")
      (footprint "eagle-import:.0603-B-NOSILK")
      (fields (field (name "MPN") "RC1608F473CS"))
      (libsource (lib "eagle-import") (part "R-US_0603-B-NOSILK"))
    )
    (comp (ref "R59")
      (value "47k")
      (footprint "eagle-import:.0603-B-NOSILK")
      (fields (field (name "MPN") "RC1608F473CS"))
      (libsource (lib "eagle-import") (part "R-US_0603-B-NOSILK"))
    )
    (comp (ref "R60")
      (value "0 Ohm")
      (footprint "eagle-import:.0603-B-NOSILK")
      (fields (field (name "MPN") "4-1676481-5"))
      (libsource (lib "eagle-import") (part "R-US_0603-B-NOSILK"))
    )
    (comp (ref "R61")
      (value "390")
      (footprint "eagle-import:.0603-B-NOSILK")
      (fields (field (name "MPN") "4-1676481-5"))
      (libsource (lib "eagle-import") (part "R-US_0603-B-NOSILK"))
    )
    (comp (ref "R62")
      (value "1k")
      (footprint "eagle-import:.0603-B-NOSILK")
      (fields (field (name "MPN") "4-1676481-5"))
      (libsource (lib "eagle-import") (part "R-US_0603-B-NOSILK"))
    )
    (comp (ref "R63")
      (value "DNP/1k")
      (footprint "eagle-import:.0603-B-NOSILK")
      (fields (field (name "MPN") "RC1608F102CS"))
      (libsource (lib "eagle-import") (part "R-US_0603-B-NOSILK"))
    )
    (comp (ref "R64")
      (value "47k")
      (footprint "eagle-import:.0603-B-NOSILK")
      (fields (field (name "MPN") "RC1608F473CS"))
      (libsource (lib "eagle-import") (part "R-US_0603-B-NOSILK"))
    )
    (comp (ref "R65")
      (value "93.1k")
      (footprint "eagle-import:.0603-B-NOSILK")
      (fields (field (name "MPN") "RC1608F9312CS"))
      (libsource (lib "eagle-import") (part "R-US_0603-B-NOSILK"))
    )
    (comp (ref "R66")
      (value "DNP/1k")
      (footprint "eagle-import:.0603-B-NOSILK")
      (fields (field (name "MPN") "RC1608F102CS"))
      (libsource (lib "eagle-import") (part "R-US_0603-B-NOSILK"))
    )
    (comp (ref "R67")
      (value "4.7k")
      (footprint "eagle-import:.0603-B-NOSILK")
      (fields (field (name "MPN") "RC1608F472CS"))
      (libsource (lib "eagle-import") (part "R-US_0603-B-NOSILK"))
    )
    (comp (ref "R68")
      (value "47k")
      (footprint "eagle-import:.0603-B-NOSILK")
      (fields (field (name "MPN") "RC1608F473CS"))
      (libsource (lib "eagle-import") (part "R-US_0603-B-NOSILK"))
    )
    (comp (ref "R69")
      (value "47k")
      (footprint "eagle-import:.0603-B-NOSILK")
      (fields (field (name "MPN") "RC1608F473CS"))
      (libsource (lib "eagle-import") (part "R-US_0603-B-NOSILK"))
    )
    (comp (ref "R70")
      (value "390")
      (footprint "eagle-import:.0603-B-NOSILK")
      (fields (field (name "MPN") "4-1676481-5"))
      (libsource (lib "eagle-import") (part "R-US_0603-B-NOSILK"))
    )
    (comp (ref "R71")
      (value "DNP/1k")
      (footprint "eagle-import:.0603-B-NOSILK")
      (fields (field (name "MPN") "RC1608F102CS"))
      (libsource (lib "eagle-import") (part "R-US_0603-B-NOSILK"))
    )
    (comp (ref "R72")
      (value "0 Ohm")
      (footprint "eagle-import:.0603-B-NOSILK")
      (fields (field (name "MPN") "4-1676481-5"))
      (libsource (lib "eagle-import") (part "R-US_0603-B-NOSILK"))
    )
    (comp (ref "R73")
      (value "1k")
      (footprint "eagle-import:.0603-B-NOSILK")
      (fields (field (name "MPN") "4-1676481-5"))
      (libsource (lib "eagle-import") (part "R-US_0603-B-NOSILK"))
    )
    (comp (ref "R74")
      (value "390")
      (footprint "eagle-import:.0603-B-NOSILK")
      (fields (field (name "MPN") "4-1676481-5"))
      (libsource (lib "eagle-import") (part "R-US_0603-B-NOSILK"))
    )
    (comp (ref "R75")
      (value "DNP/1k")
      (footprint "eagle-import:.0603-B-NOSILK")
      (fields (field (name "MPN") "RC1608F102CS"))
      (libsource (lib "eagle-import") (part "R-US_0603-B-NOSILK"))
    )
    (comp (ref "R76")
      (value "DNP/1k")
      (footprint "eagle-import:.0603-B-NOSILK")
      (fields (field (name "MPN") "RC1608F102CS"))
      (libsource (lib "eagle-import") (part "R-US_0603-B-NOSILK"))
    )
    (comp (ref "RILIM1")
      (value "47k")
      (footprint "eagle-import:.0603-B-NOSILK")
      (fields (field (name "MPN") "RC1608F473CS"))
      (libsource (lib "eagle-import") (part "R-US_0603-B-NOSILK"))
    )
    (comp (ref "RILIM2")
      (value "47k")
      (footprint "eagle-import:.0603-B-NOSILK")
      (fields (field (name "MPN") "RC1608F473CS"))
      (libsource (lib "eagle-import") (part "R-US_0603-B-NOSILK"))
    )
    (comp (ref "RILIM3")
      (value "47k")
      (footprint "eagle-import:.0603-B-NOSILK")
      (fields (field (name "MPN") "RC1608F473CS"))
      (libsource (lib "eagle-import") (part "R-US_0603-B-NOSILK"))
    )
    (comp (ref "RILIM4")
      (value "47k")
      (footprint "eagle-import:.0603-B-NOSILK")
      (fields (field (name "MPN") "RC1608F473CS"))
      (libsource (lib "eagle-import") (part "R-US_0603-B-NOSILK"))
    )
    (comp (ref "RILIM5")
      (value "47k")
      (footprint "eagle-import:.0603-B-NOSILK")
      (fields (field (name "MPN") "RC1608F473CS"))
      (libsource (lib "eagle-import") (part "R-US_0603-B-NOSILK"))
    )
    (comp (ref "RILIM6")
      (value "47k")
      (footprint "eagle-import:.0603-B-NOSILK")
      (fields (field (name "MPN") "RC1608F473CS"))
      (libsource (lib "eagle-import") (part "R-US_0603-B-NOSILK"))
    )
    (comp (ref "RILIM7")
      (value "47k")
      (footprint "eagle-import:.0603-B-NOSILK")
      (fields (field (name "MPN") "RC1608F473CS"))
      (libsource (lib "eagle-import") (part "R-US_0603-B-NOSILK"))
    )
    (comp (ref "RILIM8")
      (value "47k")
      (footprint "eagle-import:.0603-B-NOSILK")
      (fields (field (name "MPN") "RC1608F473CS"))
      (libsource (lib "eagle-import") (part "R-US_0603-B-NOSILK"))
    )
    (comp (ref "RIMON1")
      (value "30k")
      (footprint "eagle-import:.0603-B-NOSILK")
      (fields (field (name "MPN") "RC1608F3012CS"))
      (libsource (lib "eagle-import") (part "R-US_0603-B-NOSILK"))
    )
    (comp (ref "RIMON2")
      (value "30k")
      (footprint "eagle-import:.0603-B-NOSILK")
      (fields (field (name "MPN") "RC1608F3012CS"))
      (libsource (lib "eagle-import") (part "R-US_0603-B-NOSILK"))
    )
    (comp (ref "RIMON3")
      (value "30k")
      (footprint "eagle-import:.0603-B-NOSILK")
      (fields (field (name "MPN") "RC1608F3012CS"))
      (libsource (lib "eagle-import") (part "R-US_0603-B-NOSILK"))
    )
    (comp (ref "RIMON4")
      (value "30k")
      (footprint "eagle-import:.0603-B-NOSILK")
      (fields (field (name "MPN") "RC1608F3012CS"))
      (libsource (lib "eagle-import") (part "R-US_0603-B-NOSILK"))
    )
    (comp (ref "RIMON5")
      (value "30k")
      (footprint "eagle-import:.0603-B-NOSILK")
      (fields (field (name "MPN") "RC1608F3012CS"))
      (libsource (lib "eagle-import") (part "R-US_0603-B-NOSILK"))
    )
    (comp (ref "RIMON6")
      (value "30k")
      (footprint "eagle-import:.0603-B-NOSILK")
      (fields (field (name "MPN") "RC1608F3012CS"))
      (libsource (lib "eagle-import") (part "R-US_0603-B-NOSILK"))
    )
    (comp (ref "RIMON7")
      (value "30k")
      (footprint "eagle-import:.0603-B-NOSILK")
      (fields (field (name "MPN") "RC1608F3012CS"))
      (libsource (lib "eagle-import") (part "R-US_0603-B-NOSILK"))
    )
    (comp (ref "RIMON8")
      (value "30k")
      (footprint "eagle-import:.0603-B-NOSILK")
      (fields (field (name "MPN") "RC1608F3012CS"))
      (libsource (lib "eagle-import") (part "R-US_0603-B-NOSILK"))
    )
    (comp (ref "TP0GOOD")
      (value "TEST-POINT")
      (footprint "eagle-import:2MM-TEST-POINT")
      (libsource (lib "eagle-import") (part "TEST-POINT"))
    )
    (comp (ref "TP1GOOD")
      (value "TEST-POINT")
      (footprint "eagle-import:2MM-TEST-POINT")
      (libsource (lib "eagle-import") (part "TEST-POINT"))
    )
    (comp (ref "TP2")
      (value "TEST-POINT")
      (footprint "eagle-import:2MM-TEST-POINT")
      (libsource (lib "eagle-import") (part "TEST-POINT"))
    )
    (comp (ref "TP2GOOD")
      (value "TEST-POINT")
      (footprint "eagle-import:2MM-TEST-POINT")
      (libsource (lib "eagle-import") (part "TEST-POINT"))
    )
    (comp (ref "TP3")
      (value "TEST-POINT")
      (footprint "eagle-import:2MM-TEST-POINT")
      (libsource (lib "eagle-import") (part "TEST-POINT"))
    )
    (comp (ref "TP3GOOD")
      (value "TEST-POINT")
      (footprint "eagle-import:2MM-TEST-POINT")
      (libsource (lib "eagle-import") (part "TEST-POINT"))
    )
    (comp (ref "TP4")
      (value "TEST-POINT")
      (footprint "eagle-import:2MM-TEST-POINT")
      (libsource (lib "eagle-import") (part "TEST-POINT"))
    )
    (comp (ref "TP4GOOD")
      (value "TEST-POINT")
      (footprint "eagle-import:2MM-TEST-POINT")
      (libsource (lib "eagle-import") (part "TEST-POINT"))
    )
    (comp (ref "TP5")
      (value "TEST-POINT")
      (footprint "eagle-import:2MM-TEST-POINT")
      (libsource (lib "eagle-import") (part "TEST-POINT"))
    )
    (comp (ref "TP5GOOD")
      (value "TEST-POINT")
      (footprint "eagle-import:2MM-TEST-POINT")
      (libsource (lib "eagle-import") (part "TEST-POINT"))
    )
    (comp (ref "TP6")
      (value "TEST-POINT")
      (footprint "eagle-import:2MM-TEST-POINT")
      (libsource (lib "eagle-import") (part "TEST-POINT"))
    )
    (comp (ref "TP6GOOD")
      (value "TEST-POINT")
      (footprint "eagle-import:2MM-TEST-POINT")
      (libsource (lib "eagle-import") (part "TEST-POINT"))
    )
    (comp (ref "TP7")
      (value "TEST-POINT")
      (footprint "eagle-import:2MM-TEST-POINT")
      (libsource (lib "eagle-import") (part "TEST-POINT"))
    )
    (comp (ref "TP7GOOD")
      (value "TEST-POINT")
      (footprint "eagle-import:2MM-TEST-POINT")
      (libsource (lib "eagle-import") (part "TEST-POINT"))
    )
    (comp (ref "TP8")
      (value "TEST-POINT")
      (footprint "eagle-import:2MM-TEST-POINT")
      (libsource (lib "eagle-import") (part "TEST-POINT"))
    )
    (comp (ref "TP9")
      (value "TEST-POINT")
      (footprint "eagle-import:2MM-TEST-POINT")
      (libsource (lib "eagle-import") (part "TEST-POINT"))
    )
    (comp (ref "TP10")
      (value "TEST-POINT")
      (footprint "eagle-import:2MM-TEST-POINT")
      (libsource (lib "eagle-import") (part "TEST-POINT"))
    )
    (comp (ref "TP11")
      (value "TEST-POINT")
      (footprint "eagle-import:2MM-TEST-POINT")
      (libsource (lib "eagle-import") (part "TEST-POINT"))
    )
    (comp (ref "TP12")
      (value "TEST-POINT")
      (footprint "eagle-import:2MM-TEST-POINT")
      (libsource (lib "eagle-import") (part "TEST-POINT"))
    )
    (comp (ref "TP13")
      (value "TEST-POINT")
      (footprint "eagle-import:2MM-TEST-POINT")
      (libsource (lib "eagle-import") (part "TEST-POINT"))
    )
    (comp (ref "TP14")
      (value "TEST-POINT")
      (footprint "eagle-import:2MM-TEST-POINT")
      (libsource (lib "eagle-import") (part "TEST-POINT"))
    )
    (comp (ref "TP15")
      (value "TEST-POINT")
      (footprint "eagle-import:2MM-TEST-POINT")
      (libsource (lib "eagle-import") (part "TEST-POINT"))
    )
    (comp (ref "TP16")
      (value "TEST-POINT")
      (footprint "eagle-import:2MM-TEST-POINT")
      (libsource (lib "eagle-import") (part "TEST-POINT"))
    )
    (comp (ref "TP17")
      (value "TEST-POINT")
      (footprint "eagle-import:2MM-TEST-POINT")
      (libsource (lib "eagle-import") (part "TEST-POINT"))
    )
    (comp (ref "TP18")
      (value "TEST-POINT")
      (footprint "eagle-import:2MM-TEST-POINT")
      (libsource (lib "eagle-import") (part "TEST-POINT"))
    )
    (comp (ref "TP19")
      (value "TEST-POINT")
      (footprint "eagle-import:2MM-TEST-POINT")
      (libsource (lib "eagle-import") (part "TEST-POINT"))
    )
    (comp (ref "TP20")
      (value "TEST-POINT")
      (footprint "eagle-import:2MM-TEST-POINT")
      (libsource (lib "eagle-import") (part "TEST-POINT"))
    )
    (comp (ref "TP21")
      (value "TEST-POINT")
      (footprint "eagle-import:2MM-TEST-POINT")
      (libsource (lib "eagle-import") (part "TEST-POINT"))
    )
    (comp (ref "TP22")
      (value "TEST-POINT")
      (footprint "eagle-import:2MM-TEST-POINT")
      (libsource (lib "eagle-import") (part "TEST-POINT"))
    )
    (comp (ref "TP23")
      (value "TEST-POINT")
      (footprint "eagle-import:2MM-TEST-POINT")
      (libsource (lib "eagle-import") (part "TEST-POINT"))
    )
    (comp (ref "TP24")
      (value "TEST-POINT")
      (footprint "eagle-import:2MM-TEST-POINT")
      (libsource (lib "eagle-import") (part "TEST-POINT"))
    )
    (comp (ref "TP25")
      (value "TEST-POINT")
      (footprint "eagle-import:2MM-TEST-POINT")
      (libsource (lib "eagle-import") (part "TEST-POINT"))
    )
    (comp (ref "TP26")
      (value "TEST-POINT")
      (footprint "eagle-import:2MM-TEST-POINT")
      (libsource (lib "eagle-import") (part "TEST-POINT"))
    )
    (comp (ref "TP27")
      (value "TEST-POINT")
      (footprint "eagle-import:2MM-TEST-POINT")
      (libsource (lib "eagle-import") (part "TEST-POINT"))
    )
    (comp (ref "TP28")
      (value "TEST-POINT")
      (footprint "eagle-import:2MM-TEST-POINT")
      (libsource (lib "eagle-import") (part "TEST-POINT"))
    )
    (comp (ref "TP29")
      (value "TEST-POINT")
      (footprint "eagle-import:2MM-TEST-POINT")
      (libsource (lib "eagle-import") (part "TEST-POINT"))
    )
    (comp (ref "TP30")
      (value "TEST-POINT")
      (footprint "eagle-import:2MM-TEST-POINT")
      (libsource (lib "eagle-import") (part "TEST-POINT"))
    )
    (comp (ref "TP31")
      (value "TEST-POINT")
      (footprint "eagle-import:2MM-TEST-POINT")
      (libsource (lib "eagle-import") (part "TEST-POINT"))
    )
    (comp (ref "TP32")
      (value "TEST-POINT")
      (footprint "eagle-import:2MM-TEST-POINT")
      (libsource (lib "eagle-import") (part "TEST-POINT"))
    )
    (comp (ref "TP33")
      (value "TEST-POINT")
      (footprint "eagle-import:2MM-TEST-POINT")
      (libsource (lib "eagle-import") (part "TEST-POINT"))
    )
    (comp (ref "TP34")
      (value "TEST-POINT")
      (footprint "eagle-import:2MM-TEST-POINT")
      (libsource (lib "eagle-import") (part "TEST-POINT"))
    )
    (comp (ref "TP43")
      (value "TEST-POINT")
      (footprint "eagle-import:2MM-TEST-POINT")
      (libsource (lib "eagle-import") (part "TEST-POINT"))
    )
    (comp (ref "TP44")
      (value "TEST-POINT")
      (footprint "eagle-import:2MM-TEST-POINT")
      (libsource (lib "eagle-import") (part "TEST-POINT"))
    )
    (comp (ref "TP45")
      (value "TEST-POINT")
      (footprint "eagle-import:2MM-TEST-POINT")
      (libsource (lib "eagle-import") (part "TEST-POINT"))
    )
    (comp (ref "TP46")
      (value "TEST-POINT")
      (footprint "eagle-import:2MM-TEST-POINT")
      (libsource (lib "eagle-import") (part "TEST-POINT"))
    )
    (comp (ref "TP47")
      (value "TEST-POINT")
      (footprint "eagle-import:2MM-TEST-POINT")
      (libsource (lib "eagle-import") (part "TEST-POINT"))
    )
    (comp (ref "TP48")
      (value "TEST-POINT")
      (footprint "eagle-import:2MM-TEST-POINT")
      (libsource (lib "eagle-import") (part "TEST-POINT"))
    )
    (comp (ref "TP49")
      (value "TEST-POINT")
      (footprint "eagle-import:2MM-TEST-POINT")
      (libsource (lib "eagle-import") (part "TEST-POINT"))
    )
    (comp (ref "TP50")
      (value "TEST-POINT")
      (footprint "eagle-import:2MM-TEST-POINT")
      (libsource (lib "eagle-import") (part "TEST-POINT"))
    )
    (comp (ref "TP51")
      (value "TEST-POINT")
      (footprint "eagle-import:2MM-TEST-POINT")
      (libsource (lib "eagle-import") (part "TEST-POINT"))
    )
    (comp (ref "TP52")
      (value "TEST-POINT")
      (footprint "eagle-import:2MM-TEST-POINT")
      (libsource (lib "eagle-import") (part "TEST-POINT"))
    )
    (comp (ref "TP53")
      (value "TEST-POINT")
      (footprint "eagle-import:2MM-TEST-POINT")
      (libsource (lib "eagle-import") (part "TEST-POINT"))
    )
    (comp (ref "TP54")
      (value "TEST-POINT")
      (footprint "eagle-import:2MM-TEST-POINT")
      (libsource (lib "eagle-import") (part "TEST-POINT"))
    )
    (comp (ref "TP55")
      (value "TEST-POINT")
      (footprint "eagle-import:2MM-TEST-POINT")
      (libsource (lib "eagle-import") (part "TEST-POINT"))
    )
    (comp (ref "TP56")
      (value "TEST-POINT")
      (footprint "eagle-import:2MM-TEST-POINT")
      (libsource (lib "eagle-import") (part "TEST-POINT"))
    )
    (comp (ref "TPLDOA")
      (value "TEST-POINT")
      (footprint "eagle-import:2MM-TEST-POINT")
      (libsource (lib "eagle-import") (part "TEST-POINT"))
    )
    (comp (ref "U$1")
      (value "ACPL-M61L")
      (footprint "eagle-import:ACPL-M61L")
      (libsource (lib "eagle-import") (part "ACPL-M61L"))
    )
    (comp (ref "U$2")
      (value "ACPL-M61L")
      (footprint "eagle-import:ACPL-M61L")
      (libsource (lib "eagle-import") (part "ACPL-M61L"))
    )
    (comp (ref "U$3")
      (value "ACPL-M61L")
      (footprint "eagle-import:ACPL-M61L")
      (libsource (lib "eagle-import") (part "ACPL-M61L"))
    )
    (comp (ref "U$4")
      (value "ACPL-M61L")
      (footprint "eagle-import:ACPL-M61L")
      (libsource (lib "eagle-import") (part "ACPL-M61L"))
    )
    (comp (ref "U1")
      (value "TPS25944LRVCRWQFN-20-3X4")
      (footprint "eagle-import:QFN-20-L")
      (fields (field (name "MPN") "TPS25944LRVCR"))
      (libsource (lib "eagle-import") (part "TPS25944LRVCRWQFN-20-3X4"))
    )
    (comp (ref "U2")
      (value "LP5907MFX-3.0")
      (footprint "eagle-import:SOT-23")
      (fields (field (name "MPN") "LP5907MFX-3.0/NOPB"))
      (libsource (lib "eagle-import") (part "LP5907MFX-3.0"))
    )
    (comp (ref "U3")
      (value "TPS25944LRVCRWQFN-20-3X4")
      (footprint "eagle-import:QFN-20-L")
      (fields (field (name "MPN") "TPS25944LRVCR"))
      (libsource (lib "eagle-import") (part "TPS25944LRVCRWQFN-20-3X4"))
    )
    (comp (ref "U4")
      (value "TPS25944LRVCRWQFN-20-3X4")
      (footprint "eagle-import:QFN-20-L")
      (fields (field (name "MPN") "TPS25944LRVCR"))
      (libsource (lib "eagle-import") (part "TPS25944LRVCRWQFN-20-3X4"))
    )
    (comp (ref "U5")
      (value "TPS25944LRVCRWQFN-20-3X4")
      (footprint "eagle-import:QFN-20-L")
      (fields (field (name "MPN") "TPS25944LRVCR"))
      (libsource (lib "eagle-import") (part "TPS25944LRVCRWQFN-20-3X4"))
    )
    (comp (ref "U6")
      (value "TPS25944LRVCRWQFN-20-3X4")
      (footprint "eagle-import:QFN-20-L")
      (fields (field (name "MPN") "TPS25944LRVCR"))
      (libsource (lib "eagle-import") (part "TPS25944LRVCRWQFN-20-3X4"))
    )
    (comp (ref "U7")
      (value "ATMEGA128L-8A(U/N)")
      (footprint "eagle-import:TQFP64")
      (fields (field (name "MPN") "ATMEGA128-16AU"))
      (libsource (lib "eagle-import") (part "MEGA128-A"))
    )
    (comp (ref "U8")
      (value "TS4100")
      (footprint "eagle-import:QFN50P400X400X80-17N")
      (fields (field (name "MPN") "TS4100ITQ1633"))
      (libsource (lib "eagle-import") (part "TS4100"))
    )
    (comp (ref "U9")
      (value "TPS25944LRVCRWQFN-20-3X4")
      (footprint "eagle-import:QFN-20-L")
      (fields (field (name "MPN") "TPS25944LRVCR"))
      (libsource (lib "eagle-import") (part "TPS25944LRVCRWQFN-20-3X4"))
    )
    (comp (ref "U10")
      (value "TPS25944LRVCRWQFN-20-3X4")
      (footprint "eagle-import:QFN-20-L")
      (fields (field (name "MPN") "TPS25944LRVCR"))
      (libsource (lib "eagle-import") (part "TPS25944LRVCRWQFN-20-3X4"))
    )
    (comp (ref "U13")
      (value "TPS25944LRVCRWQFN-20-3X4")
      (footprint "eagle-import:QFN-20-L")
      (fields (field (name "MPN") "TPS25944LRVCR"))
      (libsource (lib "eagle-import") (part "TPS25944LRVCRWQFN-20-3X4"))
    )
    (comp (ref "X1")
      (value "8 MHz CRYSTAL-ABRACON-ABM3-SMD")
      (footprint "eagle-import:CRYSTAL-ABRACON-ABM3-SMD")
      (fields (field (name "MPN") "Abracon LLC"))
      (libsource (lib "eagle-import") (part "CRYSTAL-ABRACON-ABM3-SMD"))
    )
  )
  (nets
    (net (code "1") (name "/I2C-SCL") (class "Default")
      (node (ref "CF1") (pin "P$17") (pinfunction "17_P$17") (pintype "passive"))
      (node (ref "CF1") (pin "P$18") (pinfunction "18_P$18") (pintype "passive"))
      (node (ref "TP5") (pin "1") (pinfunction "1_1") (pintype "passive"))
      (node (ref "U7") (pin "25") (pinfunction "(SCL/INT0)PD0_25") (pintype "bidirectional"))
    )
    (net (code "2") (name "/I2C-SDA") (class "Default")
      (node (ref "CF1") (pin "P$19") (pinfunction "19_P$19") (pintype "passive"))
      (node (ref "CF1") (pin "P$20") (pinfunction "20_P$20") (pintype "passive"))
      (node (ref "TP28") (pin "1") (pinfunction "1_1") (pintype "passive"))
      (node (ref "U7") (pin "26") (pinfunction "(SDA/INT1)PD1_26") (pintype "bidirectional"))
    )
    (net (code "3") (name "/NUCLEAROPTION_OUT") (class "Default")
      (node (ref "CF1") (pin "P$15") (pinfunction "15_P$15") (pintype "passive"))
      (node (ref "CF1") (pin "P$16") (pinfunction "16_P$16") (pintype "passive"))
      (node (ref "Q3") (pin "3") (pinfunction "D_3") (pintype "bidirectional"))
      (node (ref "TP44") (pin "1") (pinfunction "1_1") (pintype "passive"))
    )
    (net (code "4") (name "/PCB3_EN") (class "Default")
      (node (ref "R29") (pin "1") (pinfunction "1_1") (pintype "passive"))
      (node (ref "TP11") (pin "1") (pinfunction "1_1") (pintype "passive"))
      (node (ref "U7") (pin "47") (pinfunction "(AD4)PA4_47") (pintype "bidirectional"))
    )
    (net (code "5") (name "/RXD0") (class "Default")
      (node (ref "Q11") (pin "1") (pinfunction "G_1") (pintype "passive"))
      (node (ref "R72") (pin "2") (pinfunction "2_2") (pintype "passive"))
      (node (ref "U7") (pin "2") (pinfunction "(RXD/PDI)PE0_2") (pintype "bidirectional"))
    )
    (net (code "6") (name "/RXD1") (class "Default")
      (node (ref "Q9") (pin "1") (pinfunction "G_1") (pintype "passive"))
      (node (ref "R60") (pin "1") (pinfunction "1_1") (pintype "passive"))
      (node (ref "U7") (pin "27") (pinfunction "(RXD1/INT2)PD2_27") (pintype "bidirectional"))
    )
    (net (code "7") (name "/TXD0") (class "Default")
      (node (ref "LED11") (pin "K") (pinfunction "K_K") (pintype "passive"))
      (node (ref "U$2") (pin "2") (pinfunction "CATHODE_2") (pintype "bidirectional"))
      (node (ref "U7") (pin "3") (pinfunction "(TXD/PDO)PE1_3") (pintype "bidirectional"))
    )
    (net (code "8") (name "/TXD1") (class "Default")
      (node (ref "LED7") (pin "K") (pinfunction "K_K") (pintype "passive"))
      (node (ref "U$1") (pin "2") (pinfunction "CATHODE_2") (pintype "bidirectional"))
      (node (ref "U7") (pin "28") (pinfunction "(TXD1/INT3)PD3_28") (pintype "bidirectional"))
    )
    (net (code "9") (name "/UART_FC_RX") (class "Default")
      (node (ref "CF1") (pin "P$23") (pinfunction "23_P$23") (pintype "passive"))
      (node (ref "CF1") (pin "P$24") (pinfunction "24_P$24") (pintype "passive"))
      (node (ref "R62") (pin "1") (pinfunction "1_1") (pintype "passive"))
      (node (ref "TP30") (pin "1") (pinfunction "1_1") (pintype "passive"))
    )
    (net (code "10") (name "/UART_FC_TX") (class "Default")
      (node (ref "CF1") (pin "P$25") (pinfunction "25_P$25") (pintype "passive"))
      (node (ref "CF1") (pin "P$26") (pinfunction "26_P$26") (pintype "passive"))
      (node (ref "TP31") (pin "1") (pinfunction "1_1") (pintype "passive"))
      (node (ref "U$3") (pin "2") (pinfunction "CATHODE_2") (pintype "bidirectional"))
    )
    (net (code "11") (name "/UART_FC_VCC") (class "Default")
      (node (ref "C27") (pin "2") (pinfunction "2_2") (pintype "passive"))
      (node (ref "CF1") (pin "P$21") (pinfunction "21_P$21") (pintype "passive"))
      (node (ref "CF1") (pin "P$22") (pinfunction "22_P$22") (pintype "passive"))
      (node (ref "TP29") (pin "1") (pinfunction "1_1") (pintype "passive"))
      (node (ref "U$1") (pin "5") (pinfunction "VDD_5") (pintype "bidirectional"))
    )
    (net (code "12") (name "/UART_LGR_RX") (class "Default")
      (node (ref "CF1") (pin "P$29") (pinfunction "29_P$29") (pintype "passive"))
      (node (ref "CF1") (pin "P$30") (pinfunction "30_P$30") (pintype "passive"))
      (node (ref "R73") (pin "1") (pinfunction "1_1") (pintype "passive"))
      (node (ref "TP33") (pin "1") (pinfunction "1_1") (pintype "passive"))
    )
    (net (code "13") (name "/UART_LGR_TX") (class "Default")
      (node (ref "CF1") (pin "P$31") (pinfunction "31_P$31") (pintype "passive"))
      (node (ref "CF1") (pin "P$32") (pinfunction "32_P$32") (pintype "passive"))
      (node (ref "TP34") (pin "1") (pinfunction "1_1") (pintype "passive"))
      (node (ref "U$4") (pin "2") (pinfunction "CATHODE_2") (pintype "bidirectional"))
    )
    (net (code "14") (name "/UART_LGR_VCC") (class "Default")
      (node (ref "C31") (pin "2") (pinfunction "2_2") (pintype "passive"))
      (node (ref "CF1") (pin "P$27") (pinfunction "27_P$27") (pintype "passive"))
      (node (ref "CF1") (pin "P$28") (pinfunction "28_P$28") (pintype "passive"))
      (node (ref "TP32") (pin "1") (pinfunction "1_1") (pintype "passive"))
      (node (ref "U$2") (pin "5") (pinfunction "VDD_5") (pintype "bidirectional"))
    )
    (net (code "15") (name "/VCB0") (class "Default")
      (node (ref "CF2") (pin "P$1") (pinfunction "1_P$1") (pintype "passive"))
      (node (ref "CF2") (pin "P$2") (pinfunction "2_P$2") (pintype "passive"))
      (node (ref "CF2") (pin "P$3") (pinfunction "3_P$3") (pintype "passive"))
      (node (ref "CF2") (pin "P$4") (pinfunction "4_P$4") (pintype "passive"))
      (node (ref "R3") (pin "1") (pinfunction "1_1") (pintype "passive"))
      (node (ref "U1") (pin "4") (pinfunction "OUT_4") (pintype "bidirectional"))
      (node (ref "U1") (pin "5") (pinfunction "OUT_5") (pintype "bidirectional"))
      (node (ref "U1") (pin "6") (pinfunction "OUT_6") (pintype "bidirectional"))
      (node (ref "U1") (pin "7") (pinfunction "OUT_7") (pintype "bidirectional"))
      (node (ref "U1") (pin "8") (pinfunction "OUT_8") (pintype "bidirectional"))
    )
    (net (code "16") (name "/VCB0_EN") (class "Default")
      (node (ref "R4") (pin "1") (pinfunction "1_1") (pintype "passive"))
      (node (ref "TP14") (pin "1") (pinfunction "1_1") (pintype "passive"))
      (node (ref "U7") (pin "44") (pinfunction "(AD7)PA7_44") (pintype "bidirectional"))
    )
    (net (code "17") (name "/VCB0_~{FLT}") (class "Default")
      (node (ref "R32") (pin "2") (pinfunction "2_2") (pintype "passive"))
      (node (ref "TP26") (pin "1") (pinfunction "1_1") (pintype "passive"))
      (node (ref "U1") (pin "20") (pinfunction "~{FLT}_20") (pintype "bidirectional"))
      (node (ref "U7") (pin "42") (pinfunction "(A15)PC7_42") (pintype "bidirectional"))
    )
    (net (code "18") (name "/VCB1") (class "Default")
      (node (ref "CF2") (pin "P$5") (pinfunction "5_P$5") (pintype "passive"))
      (node (ref "CF2") (pin "P$6") (pinfunction "6_P$6") (pintype "passive"))
      (node (ref "CF2") (pin "P$7") (pinfunction "7_P$7") (pintype "passive"))
      (node (ref "CF2") (pin "P$8") (pinfunction "8_P$8") (pintype "passive"))
      (node (ref "R10") (pin "1") (pinfunction "1_1") (pintype "passive"))
      (node (ref "U3") (pin "4") (pinfunction "OUT_4") (pintype "bidirectional"))
      (node (ref "U3") (pin "5") (pinfunction "OUT_5") (pintype "bidirectional"))
      (node (ref "U3") (pin "6") (pinfunction "OUT_6") (pintype "bidirectional"))
      (node (ref "U3") (pin "7") (pinfunction "OUT_7") (pintype "bidirectional"))
      (node (ref "U3") (pin "8") (pinfunction "OUT_8") (pintype "bidirectional"))
    )
    (net (code "19") (name "/VCB1_EN") (class "Default")
      (node (ref "R11") (pin "1") (pinfunction "1_1") (pintype "passive"))
      (node (ref "TP13") (pin "1") (pinfunction "1_1") (pintype "passive"))
      (node (ref "U7") (pin "45") (pinfunction "(AD6)PA6_45") (pintype "bidirectional"))
    )
    (net (code "20") (name "/VCB1_~{FLT}") (class "Default")
      (node (ref "R33") (pin "2") (pinfunction "2_2") (pintype "passive"))
      (node (ref "TP25") (pin "1") (pinfunction "1_1") (pintype "passive"))
      (node (ref "U3") (pin "20") (pinfunction "~{FLT}_20") (pintype "bidirectional"))
      (node (ref "U7") (pin "41") (pinfunction "(A14)PC6_41") (pintype "bidirectional"))
    )
    (net (code "21") (name "/VCB2") (class "Default")
      (node (ref "CF2") (pin "P$11") (pinfunction "11_P$11") (pintype "passive"))
      (node (ref "CF2") (pin "P$12") (pinfunction "12_P$12") (pintype "passive"))
      (node (ref "CF2") (pin "P$13") (pinfunction "13_P$13") (pintype "passive"))
      (node (ref "CF2") (pin "P$14") (pinfunction "14_P$14") (pintype "passive"))
      (node (ref "R21") (pin "1") (pinfunction "1_1") (pintype "passive"))
      (node (ref "U4") (pin "4") (pinfunction "OUT_4") (pintype "bidirectional"))
      (node (ref "U4") (pin "5") (pinfunction "OUT_5") (pintype "bidirectional"))
      (node (ref "U4") (pin "6") (pinfunction "OUT_6") (pintype "bidirectional"))
      (node (ref "U4") (pin "7") (pinfunction "OUT_7") (pintype "bidirectional"))
      (node (ref "U4") (pin "8") (pinfunction "OUT_8") (pintype "bidirectional"))
    )
    (net (code "22") (name "/VCB2_EN") (class "Default")
      (node (ref "R22") (pin "1") (pinfunction "1_1") (pintype "passive"))
      (node (ref "TP12") (pin "1") (pinfunction "1_1") (pintype "passive"))
      (node (ref "U7") (pin "46") (pinfunction "(AD5)PA5_46") (pintype "bidirectional"))
    )
    (net (code "23") (name "/VCB2_~{FLT}") (class "Default")
      (node (ref "R34") (pin "2") (pinfunction "2_2") (pintype "passive"))
      (node (ref "TP24") (pin "1") (pinfunction "1_1") (pintype "passive"))
      (node (ref "U4") (pin "20") (pinfunction "~{FLT}_20") (pintype "bidirectional"))
      (node (ref "U7") (pin "40") (pinfunction "(A13)PC5_40") (pintype "bidirectional"))
    )
    (net (code "24") (name "/VCB3") (class "Default")
      (node (ref "CF2") (pin "P$15") (pinfunction "15_P$15") (pintype "passive"))
      (node (ref "CF2") (pin "P$16") (pinfunction "16_P$16") (pintype "passive"))
      (node (ref "CF2") (pin "P$17") (pinfunction "17_P$17") (pintype "passive"))
      (node (ref "CF2") (pin "P$18") (pinfunction "18_P$18") (pintype "passive"))
      (node (ref "R28") (pin "1") (pinfunction "1_1") (pintype "passive"))
      (node (ref "U5") (pin "4") (pinfunction "OUT_4") (pintype "bidirectional"))
      (node (ref "U5") (pin "5") (pinfunction "OUT_5") (pintype "bidirectional"))
      (node (ref "U5") (pin "6") (pinfunction "OUT_6") (pintype "bidirectional"))
      (node (ref "U5") (pin "7") (pinfunction "OUT_7") (pintype "bidirectional"))
      (node (ref "U5") (pin "8") (pinfunction "OUT_8") (pintype "bidirectional"))
    )
    (net (code "25") (name "/VCB3_~{FLT}") (class "Default")
      (node (ref "R35") (pin "2") (pinfunction "2_2") (pintype "passive"))
      (node (ref "TP23") (pin "1") (pinfunction "1_1") (pintype "passive"))
      (node (ref "U5") (pin "20") (pinfunction "~{FLT}_20") (pintype "bidirectional"))
      (node (ref "U7") (pin "39") (pinfunction "(A12)PC4_39") (pintype "bidirectional"))
    )
    (net (code "26") (name "/VCB4") (class "Default")
      (node (ref "CF2") (pin "P$21") (pinfunction "21_P$21") (pintype "passive"))
      (node (ref "CF2") (pin "P$22") (pinfunction "22_P$22") (pintype "passive"))
      (node (ref "CF2") (pin "P$23") (pinfunction "23_P$23") (pintype "passive"))
      (node (ref "CF2") (pin "P$24") (pinfunction "24_P$24") (pintype "passive"))
      (node (ref "R42") (pin "1") (pinfunction "1_1") (pintype "passive"))
      (node (ref "U6") (pin "4") (pinfunction "OUT_4") (pintype "bidirectional"))
      (node (ref "U6") (pin "5") (pinfunction "OUT_5") (pintype "bidirectional"))
      (node (ref "U6") (pin "6") (pinfunction "OUT_6") (pintype "bidirectional"))
      (node (ref "U6") (pin "7") (pinfunction "OUT_7") (pintype "bidirectional"))
      (node (ref "U6") (pin "8") (pinfunction "OUT_8") (pintype "bidirectional"))
    )
    (net (code "27") (name "/VCB4_EN") (class "Default")
      (node (ref "R43") (pin "1") (pinfunction "1_1") (pintype "passive"))
      (node (ref "TP10") (pin "1") (pinfunction "1_1") (pintype "passive"))
      (node (ref "U7") (pin "48") (pinfunction "(AD3)PA3_48") (pintype "bidirectional"))
    )
    (net (code "28") (name "/VCB4_~{FLT}") (class "Default")
      (node (ref "R36") (pin "2") (pinfunction "2_2") (pintype "passive"))
      (node (ref "TP22") (pin "1") (pinfunction "1_1") (pintype "passive"))
      (node (ref "U6") (pin "20") (pinfunction "~{FLT}_20") (pintype "bidirectional"))
      (node (ref "U7") (pin "38") (pinfunction "(A11)PC3_38") (pintype "bidirectional"))
    )
    (net (code "29") (name "/VCB5") (class "Default")
      (node (ref "CF2") (pin "P$25") (pinfunction "25_P$25") (pintype "passive"))
      (node (ref "CF2") (pin "P$26") (pinfunction "26_P$26") (pintype "passive"))
      (node (ref "CF2") (pin "P$27") (pinfunction "27_P$27") (pintype "passive"))
      (node (ref "CF2") (pin "P$28") (pinfunction "28_P$28") (pintype "passive"))
      (node (ref "R48") (pin "1") (pinfunction "1_1") (pintype "passive"))
      (node (ref "U9") (pin "4") (pinfunction "OUT_4") (pintype "bidirectional"))
      (node (ref "U9") (pin "5") (pinfunction "OUT_5") (pintype "bidirectional"))
      (node (ref "U9") (pin "6") (pinfunction "OUT_6") (pintype "bidirectional"))
      (node (ref "U9") (pin "7") (pinfunction "OUT_7") (pintype "bidirectional"))
      (node (ref "U9") (pin "8") (pinfunction "OUT_8") (pintype "bidirectional"))
    )
    (net (code "30") (name "/VCB5_EN") (class "Default")
      (node (ref "R49") (pin "1") (pinfunction "1_1") (pintype "passive"))
      (node (ref "TP6") (pin "1") (pinfunction "1_1") (pintype "passive"))
      (node (ref "U7") (pin "49") (pinfunction "(AD2)PA2_49") (pintype "bidirectional"))
    )
    (net (code "31") (name "/VCB5_~{FLT}") (class "Default")
      (node (ref "R37") (pin "2") (pinfunction "2_2") (pintype "passive"))
      (node (ref "TP21") (pin "1") (pinfunction "1_1") (pintype "passive"))
      (node (ref "U7") (pin "37") (pinfunction "(A10)PC2_37") (pintype "bidirectional"))
      (node (ref "U9") (pin "20") (pinfunction "~{FLT}_20") (pintype "bidirectional"))
    )
    (net (code "32") (name "/VCB6") (class "Default")
      (node (ref "CF2") (pin "P$31") (pinfunction "31_P$31") (pintype "passive"))
      (node (ref "CF2") (pin "P$32") (pinfunction "32_P$32") (pintype "passive"))
      (node (ref "CF2") (pin "P$33") (pinfunction "33_P$33") (pintype "passive"))
      (node (ref "CF2") (pin "P$34") (pinfunction "34_P$34") (pintype "passive"))
      (node (ref "R56") (pin "1") (pinfunction "1_1") (pintype "passive"))
      (node (ref "U10") (pin "4") (pinfunction "OUT_4") (pintype "bidirectional"))
      (node (ref "U10") (pin "5") (pinfunction "OUT_5") (pintype "bidirectional"))
      (node (ref "U10") (pin "6") (pinfunction "OUT_6") (pintype "bidirectional"))
      (node (ref "U10") (pin "7") (pinfunction "OUT_7") (pintype "bidirectional"))
      (node (ref "U10") (pin "8") (pinfunction "OUT_8") (pintype "bidirectional"))
    )
    (net (code "33") (name "/VCB6_EN") (class "Default")
      (node (ref "R57") (pin "1") (pinfunction "1_1") (pintype "passive"))
      (node (ref "TP3") (pin "1") (pinfunction "1_1") (pintype "passive"))
      (node (ref "U7") (pin "50") (pinfunction "(AD1)PA1_50") (pintype "bidirectional"))
    )
    (net (code "34") (name "/VCB6_~{FLT}") (class "Default")
      (node (ref "R38") (pin "2") (pinfunction "2_2") (pintype "passive"))
      (node (ref "TP20") (pin "1") (pinfunction "1_1") (pintype "passive"))
      (node (ref "U10") (pin "20") (pinfunction "~{FLT}_20") (pintype "bidirectional"))
      (node (ref "U7") (pin "36") (pinfunction "(A9)PC1_36") (pintype "bidirectional"))
    )
    (net (code "35") (name "/VCB7") (class "Default")
      (node (ref "CF2") (pin "P$35") (pinfunction "35_P$35") (pintype "passive"))
      (node (ref "CF2") (pin "P$36") (pinfunction "36_P$36") (pintype "passive"))
      (node (ref "CF2") (pin "P$37") (pinfunction "37_P$37") (pintype "passive"))
      (node (ref "CF2") (pin "P$38") (pinfunction "38_P$38") (pintype "passive"))
      (node (ref "R66") (pin "1") (pinfunction "1_1") (pintype "passive"))
      (node (ref "U13") (pin "4") (pinfunction "OUT_4") (pintype "bidirectional"))
      (node (ref "U13") (pin "5") (pinfunction "OUT_5") (pintype "bidirectional"))
      (node (ref "U13") (pin "6") (pinfunction "OUT_6") (pintype "bidirectional"))
      (node (ref "U13") (pin "7") (pinfunction "OUT_7") (pintype "bidirectional"))
      (node (ref "U13") (pin "8") (pinfunction "OUT_8") (pintype "bidirectional"))
    )
    (net (code "36") (name "/VCB7_EN") (class "Default")
      (node (ref "R67") (pin "1") (pinfunction "1_1") (pintype "passive"))
      (node (ref "TP2") (pin "1") (pinfunction "1_1") (pintype "passive"))
      (node (ref "U7") (pin "51") (pinfunction "(AD0)PA0_51") (pintype "bidirectional"))
    )
    (net (code "37") (name "/VCB7_~{FLT}") (class "Default")
      (node (ref "R39") (pin "2") (pinfunction "2_2") (pintype "passive"))
      (node (ref "TP45") (pin "1") (pinfunction "1_1") (pintype "passive"))
      (node (ref "U13") (pin "20") (pinfunction "~{FLT}_20") (pintype "bidirectional"))
      (node (ref "U7") (pin "35") (pinfunction "(A8)PC0_35") (pintype "bidirectional"))
    )
    (net (code "38") (name "3V") (class "Default")
      (node (ref "C12") (pin "2") (pinfunction "2_2") (pintype "passive"))
      (node (ref "C13") (pin "2") (pinfunction "2_2") (pintype "passive"))
      (node (ref "C18") (pin "2") (pinfunction "2_2") (pintype "passive"))
      (node (ref "C23") (pin "2") (pinfunction "2_2") (pintype "passive"))
      (node (ref "C28") (pin "2") (pinfunction "2_2") (pintype "passive"))
      (node (ref "C32") (pin "2") (pinfunction "2_2") (pintype "passive"))
      (node (ref "C5") (pin "1") (pinfunction "1_1") (pintype "passive"))
      (node (ref "J1") (pin "1") (pinfunction "VDD_1") (pintype "passive"))
      (node (ref "Q11") (pin "2") (pinfunction "S_2") (pintype "passive"))
      (node (ref "Q9") (pin "2") (pinfunction "S_2") (pintype "passive"))
      (node (ref "R25") (pin "1") (pinfunction "1_1") (pintype "passive"))
      (node (ref "R32") (pin "1") (pinfunction "1_1") (pintype "passive"))
      (node (ref "R33") (pin "1") (pinfunction "1_1") (pintype "passive"))
      (node (ref "R34") (pin "1") (pinfunction "1_1") (pintype "passive"))
      (node (ref "R35") (pin "1") (pinfunction "1_1") (pintype "passive"))
      (node (ref "R36") (pin "1") (pinfunction "1_1") (pintype "passive"))
      (node (ref "R37") (pin "1") (pinfunction "1_1") (pintype "passive"))
      (node (ref "R38") (pin "1") (pinfunction "1_1") (pintype "passive"))
      (node (ref "R39") (pin "1") (pinfunction "1_1") (pintype "passive"))
      (node (ref "R52") (pin "1") (pinfunction "1_1") (pintype "passive"))
      (node (ref "R54") (pin "2") (pinfunction "2_2") (pintype "passive"))
      (node (ref "R61") (pin "2") (pinfunction "2_2") (pintype "passive"))
      (node (ref "R70") (pin "2") (pinfunction "2_2") (pintype "passive"))
      (node (ref "R71") (pin "1") (pinfunction "1_1") (pintype "passive"))
      (node (ref "R74") (pin "2") (pinfunction "2_2") (pintype "passive"))
      (node (ref "R76") (pin "1") (pinfunction "1_1") (pintype "passive"))
      (node (ref "U$3") (pin "5") (pinfunction "VDD_5") (pintype "bidirectional"))
      (node (ref "U$4") (pin "5") (pinfunction "VDD_5") (pintype "bidirectional"))
      (node (ref "U2") (pin "5") (pinfunction "VOUT_5") (pintype "bidirectional"))
      (node (ref "U7") (pin "21") (pinfunction "VCC_21") (pintype "power_in"))
      (node (ref "U7") (pin "52") (pinfunction "VCC_52") (pintype "power_in"))
      (node (ref "U7") (pin "64") (pinfunction "AVCC_64") (pintype "power_in"))
      (node (ref "U8") (pin "14") (pinfunction "VDD_14") (pintype "bidirectional"))
    )
    (net (code "39") (name "GND") (class "Default")
      (node (ref "C1") (pin "1") (pinfunction "1_1") (pintype "passive"))
      (node (ref "C10") (pin "2") (pinfunction "2_2") (pintype "passive"))
      (node (ref "C11") (pin "2") (pinfunction "2_2") (pintype "passive"))
      (node (ref "C12") (pin "1") (pinfunction "1_1") (pintype "passive"))
      (node (ref "C13") (pin "1") (pinfunction "1_1") (pintype "passive"))
      (node (ref "C14") (pin "1") (pinfunction "1_1") (pintype "passive"))
      (node (ref "C15") (pin "1") (pinfunction "1_1") (pintype "passive"))
      (node (ref "C16") (pin "2") (pinfunction "2_2") (pintype "passive"))
      (node (ref "C17") (pin "1") (pinfunction "1_1") (pintype "passive"))
      (node (ref "C18") (pin "1") (pinfunction "1_1") (pintype "passive"))
      (node (ref "C19") (pin "1") (pinfunction "1_1") (pintype "passive"))
      (node (ref "C2") (pin "2") (pinfunction "2_2") (pintype "passive"))
      (node (ref "C20") (pin "1") (pinfunction "1_1") (pintype "passive"))
      (node (ref "C21") (pin "2") (pinfunction "2_2") (pintype "passive"))
      (node (ref "C22") (pin "1") (pinfunction "1_1") (pintype "passive"))
      (node (ref "C23") (pin "1") (pinfunction "1_1") (pintype "passive"))
      (node (ref "C24") (pin "2") (pinfunction "2_2") (pintype "passive"))
      (node (ref "C25") (pin "1") (pinfunction "1_1") (pintype "passive"))
      (node (ref "C26") (pin "2") (pinfunction "2_2") (pintype "passive"))
      (node (ref "C27") (pin "1") (pinfunction "1_1") (pintype "passive"))
      (node (ref "C28") (pin "1") (pinfunction "1_1") (pintype "passive"))
      (node (ref "C29") (pin "1") (pinfunction "1_1") (pintype "passive"))
      (node (ref "C3") (pin "-") (pinfunction "-_-") (pintype "passive"))
      (node (ref "C30") (pin "2") (pinfunction "2_2") (pintype "passive"))
      (node (ref "C31") (pin "1") (pinfunction "1_1") (pintype "passive"))
      (node (ref "C32") (pin "1") (pinfunction "1_1") (pintype "passive"))
      (node (ref "C5") (pin "2") (pinfunction "2_2") (pintype "passive"))
      (node (ref "C6") (pin "1") (pinfunction "1_1") (pintype "passive"))
      (node (ref "C7") (pin "1") (pinfunction "1_1") (pintype "passive"))
      (node (ref "C8") (pin "2") (pinfunction "2_2") (pintype "passive"))
      (node (ref "C9") (pin "1") (pinfunction "1_1") (pintype "passive"))
      (node (ref "CF1") (pin "P$33") (pinfunction "33_P$33") (pintype "passive"))
      (node (ref "CF1") (pin "P$34") (pinfunction "34_P$34") (pintype "passive"))
      (node (ref "CF1") (pin "P$35") (pinfunction "35_P$35") (pintype "passive"))
      (node (ref "CF1") (pin "P$36") (pinfunction "36_P$36") (pintype "passive"))
      (node (ref "CF1") (pin "P$37") (pinfunction "37_P$37") (pintype "passive"))
      (node (ref "CF1") (pin "P$38") (pinfunction "38_P$38") (pintype "passive"))
      (node (ref "CF1") (pin "P$39") (pinfunction "39_P$39") (pintype "passive"))
      (node (ref "CF1") (pin "P$40") (pinfunction "40_P$40") (pintype "passive"))
      (node (ref "CF2") (pin "P$10") (pinfunction "10_P$10") (pintype "passive"))
      (node (ref "CF2") (pin "P$19") (pinfunction "19_P$19") (pintype "passive"))
      (node (ref "CF2") (pin "P$20") (pinfunction "20_P$20") (pintype "passive"))
      (node (ref "CF2") (pin "P$29") (pinfunction "29_P$29") (pintype "passive"))
      (node (ref "CF2") (pin "P$30") (pinfunction "30_P$30") (pintype "passive"))
      (node (ref "CF2") (pin "P$39") (pinfunction "39_P$39") (pintype "passive"))
      (node (ref "CF2") (pin "P$40") (pinfunction "40_P$40") (pintype "passive"))
      (node (ref "CF2") (pin "P$9") (pinfunction "9_P$9") (pintype "passive"))
      (node (ref "J1") (pin "3") (pinfunction "GND3_3") (pintype "passive"))
      (node (ref "J1") (pin "5") (pinfunction "GND5_5") (pintype "passive"))
      (node (ref "J1") (pin "9") (pinfunction "GND9_9") (pintype "passive"))
      (node (ref "LED1") (pin "K") (pinfunction "K_K") (pintype "passive"))
      (node (ref "LED10") (pin "K") (pinfunction "K_K") (pintype "passive"))
      (node (ref "LED12") (pin "K") (pinfunction "K_K") (pintype "passive"))
      (node (ref "LED13") (pin "K") (pinfunction "K_K") (pintype "passive"))
      (node (ref "LED2") (pin "K") (pinfunction "K_K") (pintype "passive"))
      (node (ref "LED3") (pin "K") (pinfunction "K_K") (pintype "passive"))
      (node (ref "LED4") (pin "K") (pinfunction "K_K") (pintype "passive"))
      (node (ref "LED5") (pin "K") (pinfunction "K_K") (pintype "passive"))
      (node (ref "LED6") (pin "K") (pinfunction "K_K") (pintype "passive"))
      (node (ref "LED8") (pin "K") (pinfunction "K_K") (pintype "passive"))
      (node (ref "LED9") (pin "K") (pinfunction "K_K") (pintype "passive"))
      (node (ref "Q1") (pin "5") (pinfunction "S_5") (pintype "passive"))
      (node (ref "Q10") (pin "5") (pinfunction "S_5") (pintype "passive"))
      (node (ref "Q2") (pin "5") (pinfunction "S_5") (pintype "passive"))
      (node (ref "Q3") (pin "2") (pinfunction "S_2") (pintype "bidirectional"))
      (node (ref "Q4") (pin "5") (pinfunction "S_5") (pintype "passive"))
      (node (ref "Q5") (pin "5") (pinfunction "S_5") (pintype "passive"))
      (node (ref "Q6") (pin "5") (pinfunction "S_5") (pintype "passive"))
      (node (ref "Q7") (pin "5") (pinfunction "S_5") (pintype "passive"))
      (node (ref "Q8") (pin "5") (pinfunction "S_5") (pintype "passive"))
      (node (ref "R12") (pin "2") (pinfunction "2_2") (pintype "passive"))
      (node (ref "R13") (pin "2") (pinfunction "2_2") (pintype "passive"))
      (node (ref "R18") (pin "2") (pinfunction "2_2") (pintype "passive"))
      (node (ref "R19") (pin "2") (pinfunction "2_2") (pintype "passive"))
      (node (ref "R23") (pin "2") (pinfunction "2_2") (pintype "passive"))
      (node (ref "R24") (pin "2") (pinfunction "2_2") (pintype "passive"))
      (node (ref "R30") (pin "2") (pinfunction "2_2") (pintype "passive"))
      (node (ref "R31") (pin "2") (pinfunction "2_2") (pintype "passive"))
      (node (ref "R44") (pin "2") (pinfunction "2_2") (pintype "passive"))
      (node (ref "R45") (pin "2") (pinfunction "2_2") (pintype "passive"))
      (node (ref "R5") (pin "2") (pinfunction "2_2") (pintype "passive"))
      (node (ref "R50") (pin "2") (pinfunction "2_2") (pintype "passive"))
      (node (ref "R51") (pin "2") (pinfunction "2_2") (pintype "passive"))
      (node (ref "R58") (pin "2") (pinfunction "2_2") (pintype "passive"))
      (node (ref "R59") (pin "2") (pinfunction "2_2") (pintype "passive"))
      (node (ref "R6") (pin "2") (pinfunction "2_2") (pintype "passive"))
      (node (ref "R68") (pin "2") (pinfunction "2_2") (pintype "passive"))
      (node (ref "R69") (pin "2") (pinfunction "2_2") (pintype "passive"))
      (node (ref "RILIM1") (pin "2") (pinfunction "2_2") (pintype "passive"))
      (node (ref "RILIM2") (pin "2") (pinfunction "2_2") (pintype "passive"))
      (node (ref "RILIM3") (pin "2") (pinfunction "2_2") (pintype "passive"))
      (node (ref "RILIM4") (pin "2") (pinfunction "2_2") (pintype "passive"))
      (node (ref "RILIM5") (pin "2") (pinfunction "2_2") (pintype "passive"))
      (node (ref "RILIM6") (pin "2") (pinfunction "2_2") (pintype "passive"))
      (node (ref "RILIM7") (pin "2") (pinfunction "2_2") (pintype "passive"))
      (node (ref "RILIM8") (pin "2") (pinfunction "2_2") (pintype "passive"))
      (node (ref "RIMON1") (pin "2") (pinfunction "2_2") (pintype "passive"))
      (node (ref "RIMON2") (pin "2") (pinfunction "2_2") (pintype "passive"))
      (node (ref "RIMON3") (pin "2") (pinfunction "2_2") (pintype "passive"))
      (node (ref "RIMON4") (pin "2") (pinfunction "2_2") (pintype "passive"))
      (node (ref "RIMON5") (pin "2") (pinfunction "2_2") (pintype "passive"))
      (node (ref "RIMON6") (pin "2") (pinfunction "2_2") (pintype "passive"))
      (node (ref "RIMON7") (pin "2") (pinfunction "2_2") (pintype "passive"))
      (node (ref "RIMON8") (pin "2") (pinfunction "2_2") (pintype "passive"))
      (node (ref "U$1") (pin "3") (pinfunction "GND_3") (pintype "bidirectional"))
      (node (ref "U$2") (pin "3") (pinfunction "GND_3") (pintype "bidirectional"))
      (node (ref "U$3") (pin "3") (pinfunction "GND_3") (pintype "bidirectional"))
      (node (ref "U$4") (pin "3") (pinfunction "GND_3") (pintype "bidirectional"))
      (node (ref "U1") (pin "1") (pinfunction "DMODE_1") (pintype "bidirectional"))
      (node (ref "U1") (pin "15") (pinfunction "OVP_15") (pintype "bidirectional"))
      (node (ref "U1") (pin "16") (pinfunction "GND_16") (pintype "power_in"))
      (node (ref "U1") (pin "21") (pinfunction "GND_21") (pintype "power_in"))
      (node (ref "U1") (pin "3") (pinfunction "PGHT_3") (pintype "bidirectional"))
      (node (ref "U10") (pin "1") (pinfunction "DMODE_1") (pintype "bidirectional"))
      (node (ref "U10") (pin "15") (pinfunction "OVP_15") (pintype "bidirectional"))
      (node (ref "U10") (pin "16") (pinfunction "GND_16") (pintype "power_in"))
      (node (ref "U10") (pin "21") (pinfunction "GND_21") (pintype "power_in"))
      (node (ref "U10") (pin "3") (pinfunction "PGHT_3") (pintype "bidirectional"))
      (node (ref "U13") (pin "1") (pinfunction "DMODE_1") (pintype "bidirectional"))
      (node (ref "U13") (pin "15") (pinfunction "OVP_15") (pintype "bidirectional"))
      (node (ref "U13") (pin "16") (pinfunction "GND_16") (pintype "power_in"))
      (node (ref "U13") (pin "21") (pinfunction "GND_21") (pintype "power_in"))
      (node (ref "U13") (pin "3") (pinfunction "PGHT_3") (pintype "bidirectional"))
      (node (ref "U2") (pin "2") (pinfunction "GND_2") (pintype "bidirectional"))
      (node (ref "U3") (pin "1") (pinfunction "DMODE_1") (pintype "bidirectional"))
      (node (ref "U3") (pin "15") (pinfunction "OVP_15") (pintype "bidirectional"))
      (node (ref "U3") (pin "16") (pinfunction "GND_16") (pintype "power_in"))
      (node (ref "U3") (pin "21") (pinfunction "GND_21") (pintype "power_in"))
      (node (ref "U3") (pin "3") (pinfunction "PGHT_3") (pintype "bidirectional"))
      (node (ref "U4") (pin "1") (pinfunction "DMODE_1") (pintype "bidirectional"))
      (node (ref "U4") (pin "15") (pinfunction "OVP_15") (pintype "bidirectional"))
      (node (ref "U4") (pin "16") (pinfunction "GND_16") (pintype "power_in"))
      (node (ref "U4") (pin "21") (pinfunction "GND_21") (pintype "power_in"))
      (node (ref "U4") (pin "3") (pinfunction "PGHT_3") (pintype "bidirectional"))
      (node (ref "U5") (pin "1") (pinfunction "DMODE_1") (pintype "bidirectional"))
      (node (ref "U5") (pin "15") (pinfunction "OVP_15") (pintype "bidirectional"))
      (node (ref "U5") (pin "16") (pinfunction "GND_16") (pintype "power_in"))
      (node (ref "U5") (pin "21") (pinfunction "GND_21") (pintype "power_in"))
      (node (ref "U5") (pin "3") (pinfunction "PGHT_3") (pintype "bidirectional"))
      (node (ref "U6") (pin "1") (pinfunction "DMODE_1") (pintype "bidirectional"))
      (node (ref "U6") (pin "15") (pinfunction "OVP_15") (pintype "bidirectional"))
      (node (ref "U6") (pin "16") (pinfunction "GND_16") (pintype "power_in"))
      (node (ref "U6") (pin "21") (pinfunction "GND_21") (pintype "power_in"))
      (node (ref "U6") (pin "3") (pinfunction "PGHT_3") (pintype "bidirectional"))
      (node (ref "U7") (pin "22") (pinfunction "GND_22") (pintype "power_in"))
      (node (ref "U7") (pin "53") (pinfunction "GND_53") (pintype "power_in"))
      (node (ref "U7") (pin "63") (pinfunction "GND_63") (pintype "power_in"))
      (node (ref "U8") (pin "17") (pinfunction "GND_17") (pintype "bidirectional"))
      (node (ref "U8") (pin "4") (pinfunction "INH_4") (pintype "bidirectional"))
      (node (ref "U8") (pin "6") (pinfunction "GND_6") (pintype "bidirectional"))
      (node (ref "U9") (pin "1") (pinfunction "DMODE_1") (pintype "bidirectional"))
      (node (ref "U9") (pin "15") (pinfunction "OVP_15") (pintype "bidirectional"))
      (node (ref "U9") (pin "16") (pinfunction "GND_16") (pintype "power_in"))
      (node (ref "U9") (pin "21") (pinfunction "GND_21") (pintype "power_in"))
      (node (ref "U9") (pin "3") (pinfunction "PGHT_3") (pintype "bidirectional"))
    )
    (net (code "40") (name "NUCLEAROPTION0") (class "Default")
      (node (ref "R16") (pin "2") (pinfunction "2_2") (pintype "passive"))
      (node (ref "U7") (pin "33") (pinfunction "PG0(WR)_33") (pintype "bidirectional"))
    )
    (net (code "41") (name "NUCLEAROPTION1") (class "Default")
      (node (ref "R15") (pin "2") (pinfunction "2_2") (pintype "passive"))
      (node (ref "U7") (pin "34") (pinfunction "PG1(RD)_34") (pintype "bidirectional"))
    )
    (net (code "42") (name "NUCLEAROPTION2") (class "Default")
      (node (ref "R14") (pin "2") (pinfunction "2_2") (pintype "passive"))
      (node (ref "U7") (pin "43") (pinfunction "PG2(ALE)_43") (pintype "bidirectional"))
    )
    (net (code "43") (name "Net-(D3-+)") (class "Default")
      (node (ref "D3") (pin "1") (pinfunction "+_1") (pintype "passive"))
      (node (ref "R14") (pin "1") (pinfunction "1_1") (pintype "passive"))
      (node (ref "R15") (pin "1") (pinfunction "1_1") (pintype "passive"))
      (node (ref "R16") (pin "1") (pinfunction "1_1") (pintype "passive"))
      (node (ref "R19") (pin "1") (pinfunction "1_1") (pintype "passive"))
      (node (ref "TP43") (pin "1") (pinfunction "1_1") (pintype "passive"))
    )
    (net (code "44") (name "Net-(D3--)") (class "Default")
      (node (ref "C10") (pin "1") (pinfunction "1_1") (pintype "passive"))
      (node (ref "D3") (pin "2") (pinfunction "-_2") (pintype "passive"))
      (node (ref "Q3") (pin "1") (pinfunction "G_1") (pintype "bidirectional"))
      (node (ref "R18") (pin "1") (pinfunction "1_1") (pintype "passive"))
    )
    (net (code "45") (name "Net-(J1-SRST)") (class "Default")
      (node (ref "J1") (pin "10") (pinfunction "SRST_10") (pintype "passive"))
      (node (ref "R25") (pin "2") (pinfunction "2_2") (pintype "passive"))
      (node (ref "U7") (pin "20") (pinfunction "RESET_20") (pintype "input"))
    )
    (net (code "46") (name "Net-(J1-TCK)") (class "Default")
      (node (ref "J1") (pin "4") (pinfunction "TCK_4") (pintype "passive"))
      (node (ref "U7") (pin "57") (pinfunction "PF4(ADC4/TCK)_57") (pintype "bidirectional"))
    )
    (net (code "47") (name "Net-(J1-TDI)") (class "Default")
      (node (ref "J1") (pin "8") (pinfunction "TDI_8") (pintype "passive"))
      (node (ref "U7") (pin "54") (pinfunction "PF7(ADC7/TDI)_54") (pintype "bidirectional"))
    )
    (net (code "48") (name "Net-(J1-TDO)") (class "Default")
      (node (ref "J1") (pin "6") (pinfunction "TDO_6") (pintype "passive"))
      (node (ref "U7") (pin "55") (pinfunction "PF6(ADC6/TDO)_55") (pintype "bidirectional"))
    )
    (net (code "49") (name "Net-(J1-TMS)") (class "Default")
      (node (ref "J1") (pin "2") (pinfunction "TMS_2") (pintype "passive"))
      (node (ref "U7") (pin "56") (pinfunction "PF5(ADC5/TMS)_56") (pintype "bidirectional"))
    )
    (net (code "50") (name "Net-(LED1-PadA)") (class "Default")
      (node (ref "LED1") (pin "A") (pinfunction "A_A") (pintype "passive"))
      (node (ref "R3") (pin "2") (pinfunction "2_2") (pintype "passive"))
    )
    (net (code "51") (name "Net-(LED2-PadA)") (class "Default")
      (node (ref "LED2") (pin "A") (pinfunction "A_A") (pintype "passive"))
      (node (ref "R10") (pin "2") (pinfunction "2_2") (pintype "passive"))
    )
    (net (code "52") (name "Net-(LED3-PadA)") (class "Default")
      (node (ref "LED3") (pin "A") (pinfunction "A_A") (pintype "passive"))
      (node (ref "R21") (pin "2") (pinfunction "2_2") (pintype "passive"))
    )
    (net (code "53") (name "Net-(LED4-PadA)") (class "Default")
      (node (ref "LED4") (pin "A") (pinfunction "A_A") (pintype "passive"))
      (node (ref "R28") (pin "2") (pinfunction "2_2") (pintype "passive"))
    )
    (net (code "54") (name "Net-(LED5-PadA)") (class "Default")
      (node (ref "LED5") (pin "A") (pinfunction "A_A") (pintype "passive"))
      (node (ref "R42") (pin "2") (pinfunction "2_2") (pintype "passive"))
    )
    (net (code "55") (name "Net-(LED6-PadA)") (class "Default")
      (node (ref "LED6") (pin "A") (pinfunction "A_A") (pintype "passive"))
      (node (ref "R48") (pin "2") (pinfunction "2_2") (pintype "passive"))
    )
    (net (code "56") (name "Net-(LED7-PadA)") (class "Default")
      (node (ref "LED7") (pin "A") (pinfunction "A_A") (pintype "passive"))
      (node (ref "R52") (pin "2") (pinfunction "2_2") (pintype "passive"))
    )
    (net (code "57") (name "Net-(LED8-PadA)") (class "Default")
      (node (ref "LED8") (pin "A") (pinfunction "A_A") (pintype "passive"))
      (node (ref "R56") (pin "2") (pinfunction "2_2") (pintype "passive"))
    )
    (net (code "58") (name "Net-(LED9-PadA)") (class "Default")
      (node (ref "LED9") (pin "A") (pinfunction "A_A") (pintype "passive"))
      (node (ref "R63") (pin "2") (pinfunction "2_2") (pintype "passive"))
    )
    (net (code "59") (name "Net-(LED10-PadA)") (class "Default")
      (node (ref "LED10") (pin "A") (pinfunction "A_A") (pintype "passive"))
      (node (ref "R66") (pin "2") (pinfunction "2_2") (pintype "passive"))
    )
    (net (code "60") (name "Net-(LED11-PadA)") (class "Default")
      (node (ref "LED11") (pin "A") (pinfunction "A_A") (pintype "passive"))
      (node (ref "R71") (pin "2") (pinfunction "2_2") (pintype "passive"))
    )
    (net (code "61") (name "Net-(LED12-PadA)") (class "Default")
      (node (ref "LED12") (pin "A") (pinfunction "A_A") (pintype "passive"))
      (node (ref "R75") (pin "2") (pinfunction "2_2") (pintype "passive"))
    )
    (net (code "62") (name "Net-(LED13-PadA)") (class "Default")
      (node (ref "LED13") (pin "A") (pinfunction "A_A") (pintype "passive"))
      (node (ref "R76") (pin "2") (pinfunction "2_2") (pintype "passive"))
    )
    (net (code "63") (name "Net-(Q1A-D)") (class "Default")
      (node (ref "Q1") (pin "3") (pinfunction "G_3") (pintype "passive"))
      (node (ref "Q1") (pin "6") (pinfunction "D_6") (pintype "passive"))
      (node (ref "R1") (pin "2") (pinfunction "2_2") (pintype "passive"))
    )
    (net (code "64") (name "Net-(Q1A-G)") (class "Default")
      (node (ref "Q1") (pin "1") (pinfunction "G_1") (pintype "passive"))
      (node (ref "R4") (pin "2") (pinfunction "2_2") (pintype "passive"))
      (node (ref "R5") (pin "1") (pinfunction "1_1") (pintype "passive"))
    )
    (net (code "65") (name "Net-(Q1B-D)") (class "Default")
      (node (ref "Q1") (pin "4") (pinfunction "D_4") (pintype "passive"))
      (node (ref "R2") (pin "1") (pinfunction "1_1") (pintype "passive"))
    )
    (net (code "66") (name "Net-(Q2A-D)") (class "Default")
      (node (ref "Q2") (pin "3") (pinfunction "G_3") (pintype "passive"))
      (node (ref "Q2") (pin "6") (pinfunction "D_6") (pintype "passive"))
      (node (ref "R8") (pin "2") (pinfunction "2_2") (pintype "passive"))
    )
    (net (code "67") (name "Net-(Q2A-G)") (class "Default")
      (node (ref "Q2") (pin "1") (pinfunction "G_1") (pintype "passive"))
      (node (ref "R11") (pin "2") (pinfunction "2_2") (pintype "passive"))
      (node (ref "R12") (pin "1") (pinfunction "1_1") (pintype "passive"))
    )
    (net (code "68") (name "Net-(Q2B-D)") (class "Default")
      (node (ref "Q2") (pin "4") (pinfunction "D_4") (pintype "passive"))
      (node (ref "R9") (pin "1") (pinfunction "1_1") (pintype "passive"))
    )
    (net (code "69") (name "Net-(Q4A-D)") (class "Default")
      (node (ref "Q4") (pin "3") (pinfunction "G_3") (pintype "passive"))
      (node (ref "Q4") (pin "6") (pinfunction "D_6") (pintype "passive"))
      (node (ref "R17") (pin "2") (pinfunction "2_2") (pintype "passive"))
    )
    (net (code "70") (name "Net-(Q4A-G)") (class "Default")
      (node (ref "Q4") (pin "1") (pinfunction "G_1") (pintype "passive"))
      (node (ref "R22") (pin "2") (pinfunction "2_2") (pintype "passive"))
      (node (ref "R23") (pin "1") (pinfunction "1_1") (pintype "passive"))
    )
    (net (code "71") (name "Net-(Q4B-D)") (class "Default")
      (node (ref "Q4") (pin "4") (pinfunction "D_4") (pintype "passive"))
      (node (ref "R20") (pin "1") (pinfunction "1_1") (pintype "passive"))
    )
    (net (code "72") (name "Net-(Q5A-D)") (class "Default")
      (node (ref "Q5") (pin "3") (pinfunction "G_3") (pintype "passive"))
      (node (ref "Q5") (pin "6") (pinfunction "D_6") (pintype "passive"))
      (node (ref "R26") (pin "2") (pinfunction "2_2") (pintype "passive"))
    )
    (net (code "73") (name "Net-(Q5A-G)") (class "Default")
      (node (ref "Q5") (pin "1") (pinfunction "G_1") (pintype "passive"))
      (node (ref "R29") (pin "2") (pinfunction "2_2") (pintype "passive"))
      (node (ref "R30") (pin "1") (pinfunction "1_1") (pintype "passive"))
    )
    (net (code "74") (name "Net-(Q5B-D)") (class "Default")
      (node (ref "Q5") (pin "4") (pinfunction "D_4") (pintype "passive"))
      (node (ref "R27") (pin "1") (pinfunction "1_1") (pintype "passive"))
    )
    (net (code "75") (name "Net-(Q6A-D)") (class "Default")
      (node (ref "Q6") (pin "3") (pinfunction "G_3") (pintype "passive"))
      (node (ref "Q6") (pin "6") (pinfunction "D_6") (pintype "passive"))
      (node (ref "R40") (pin "2") (pinfunction "2_2") (pintype "passive"))
    )
    (net (code "76") (name "Net-(Q6A-G)") (class "Default")
      (node (ref "Q6") (pin "1") (pinfunction "G_1") (pintype "passive"))
      (node (ref "R43") (pin "2") (pinfunction "2_2") (pintype "passive"))
      (node (ref "R44") (pin "1") (pinfunction "1_1") (pintype "passive"))
    )
    (net (code "77") (name "Net-(Q6B-D)") (class "Default")
      (node (ref "Q6") (pin "4") (pinfunction "D_4") (pintype "passive"))
      (node (ref "R41") (pin "1") (pinfunction "1_1") (pintype "passive"))
    )
    (net (code "78") (name "Net-(Q7A-D)") (class "Default")
      (node (ref "Q7") (pin "3") (pinfunction "G_3") (pintype "passive"))
      (node (ref "Q7") (pin "6") (pinfunction "D_6") (pintype "passive"))
      (node (ref "R46") (pin "2") (pinfunction "2_2") (pintype "passive"))
    )
    (net (code "79") (name "Net-(Q7A-G)") (class "Default")
      (node (ref "Q7") (pin "1") (pinfunction "G_1") (pintype "passive"))
      (node (ref "R49") (pin "2") (pinfunction "2_2") (pintype "passive"))
      (node (ref "R50") (pin "1") (pinfunction "1_1") (pintype "passive"))
    )
    (net (code "80") (name "Net-(Q7B-D)") (class "Default")
      (node (ref "Q7") (pin "4") (pinfunction "D_4") (pintype "passive"))
      (node (ref "R47") (pin "1") (pinfunction "1_1") (pintype "passive"))
    )
    (net (code "81") (name "Net-(Q8A-D)") (class "Default")
      (node (ref "Q8") (pin "3") (pinfunction "G_3") (pintype "passive"))
      (node (ref "Q8") (pin "6") (pinfunction "D_6") (pintype "passive"))
      (node (ref "R53") (pin "2") (pinfunction "2_2") (pintype "passive"))
    )
    (net (code "82") (name "Net-(Q8A-G)") (class "Default")
      (node (ref "Q8") (pin "1") (pinfunction "G_1") (pintype "passive"))
      (node (ref "R57") (pin "2") (pinfunction "2_2") (pintype "passive"))
      (node (ref "R58") (pin "1") (pinfunction "1_1") (pintype "passive"))
    )
    (net (code "83") (name "Net-(Q8B-D)") (class "Default")
      (node (ref "Q8") (pin "4") (pinfunction "D_4") (pintype "passive"))
      (node (ref "R55") (pin "1") (pinfunction "1_1") (pintype "passive"))
    )
    (net (code "84") (name "Net-(Q9-D)") (class "Default")
      (node (ref "Q9") (pin "3") (pinfunction "D_3") (pintype "passive"))
      (node (ref "R63") (pin "1") (pinfunction "1_1") (pintype "passive"))
    )
    (net (code "85") (name "Net-(Q10A-D)") (class "Default")
      (node (ref "Q10") (pin "3") (pinfunction "G_3") (pintype "passive"))
      (node (ref "Q10") (pin "6") (pinfunction "D_6") (pintype "passive"))
      (node (ref "R64") (pin "2") (pinfunction "2_2") (pintype "passive"))
    )
    (net (code "86") (name "Net-(Q10A-G)") (class "Default")
      (node (ref "Q10") (pin "1") (pinfunction "G_1") (pintype "passive"))
      (node (ref "R67") (pin "2") (pinfunction "2_2") (pintype "passive"))
      (node (ref "R68") (pin "1") (pinfunction "1_1") (pintype "passive"))
    )
    (net (code "87") (name "Net-(Q10B-D)") (class "Default")
      (node (ref "Q10") (pin "4") (pinfunction "D_4") (pintype "passive"))
      (node (ref "R65") (pin "1") (pinfunction "1_1") (pintype "passive"))
    )
    (net (code "88") (name "Net-(Q11-D)") (class "Default")
      (node (ref "Q11") (pin "3") (pinfunction "D_3") (pintype "passive"))
      (node (ref "R75") (pin "1") (pinfunction "1_1") (pintype "passive"))
    )
    (net (code "89") (name "Net-(U$1-ANODE)") (class "Default")
      (node (ref "R54") (pin "1") (pinfunction "1_1") (pintype "passive"))
      (node (ref "U$1") (pin "1") (pinfunction "ANODE_1") (pintype "input"))
    )
    (net (code "90") (name "Net-(U$1-VO)") (class "Default")
      (node (ref "R62") (pin "2") (pinfunction "2_2") (pintype "passive"))
      (node (ref "U$1") (pin "4") (pinfunction "VO_4") (pintype "bidirectional"))
    )
    (net (code "91") (name "Net-(U$2-ANODE)") (class "Default")
      (node (ref "R70") (pin "1") (pinfunction "1_1") (pintype "passive"))
      (node (ref "U$2") (pin "1") (pinfunction "ANODE_1") (pintype "input"))
    )
    (net (code "92") (name "Net-(U$2-VO)") (class "Default")
      (node (ref "R73") (pin "2") (pinfunction "2_2") (pintype "passive"))
      (node (ref "U$2") (pin "4") (pinfunction "VO_4") (pintype "bidirectional"))
    )
    (net (code "93") (name "Net-(U$3-ANODE)") (class "Default")
      (node (ref "R61") (pin "1") (pinfunction "1_1") (pintype "passive"))
      (node (ref "U$3") (pin "1") (pinfunction "ANODE_1") (pintype "input"))
    )
    (net (code "94") (name "Net-(U$3-VO)") (class "Default")
      (node (ref "R60") (pin "2") (pinfunction "2_2") (pintype "passive"))
      (node (ref "U$3") (pin "4") (pinfunction "VO_4") (pintype "bidirectional"))
    )
    (net (code "95") (name "Net-(U$4-ANODE)") (class "Default")
      (node (ref "R74") (pin "1") (pinfunction "1_1") (pintype "passive"))
      (node (ref "U$4") (pin "1") (pinfunction "ANODE_1") (pintype "input"))
    )
    (net (code "96") (name "Net-(U$4-VO)") (class "Default")
      (node (ref "R72") (pin "1") (pinfunction "1_1") (pintype "passive"))
      (node (ref "U$4") (pin "4") (pinfunction "VO_4") (pintype "bidirectional"))
    )
    (net (code "97") (name "Net-(U1-DV{slash}DT)") (class "Default")
      (node (ref "C2") (pin "1") (pinfunction "1_1") (pintype "passive"))
      (node (ref "U1") (pin "18") (pinfunction "DV/DT_18") (pintype "bidirectional"))
    )
    (net (code "98") (name "Net-(U1-EN{slash}UVLO)") (class "Default")
      (node (ref "R2") (pin "2") (pinfunction "2_2") (pintype "passive"))
      (node (ref "R6") (pin "1") (pinfunction "1_1") (pintype "passive"))
      (node (ref "U1") (pin "14") (pinfunction "EN/UVLO_14") (pintype "bidirectional"))
    )
    (net (code "99") (name "Net-(U1-ILIM)") (class "Default")
      (node (ref "RILIM1") (pin "1") (pinfunction "1_1") (pintype "passive"))
      (node (ref "U1") (pin "17") (pinfunction "ILIM_17") (pintype "bidirectional"))
    )
    (net (code "100") (name "Net-(U1-PGOOD)") (class "Default")
      (node (ref "TP0GOOD") (pin "1") (pinfunction "1_1") (pintype "passive"))
      (node (ref "U1") (pin "2") (pinfunction "PGOOD_2") (pintype "bidirectional"))
    )
    (net (code "101") (name "Net-(U2-EN)") (class "Default")
      (node (ref "R7") (pin "2") (pinfunction "2_2") (pintype "passive"))
      (node (ref "TPLDOA") (pin "1") (pinfunction "1_1") (pintype "passive"))
      (node (ref "U2") (pin "3") (pinfunction "EN_3") (pintype "bidirectional"))
    )
    (net (code "102") (name "Net-(U3-DV{slash}DT)") (class "Default")
      (node (ref "C8") (pin "1") (pinfunction "1_1") (pintype "passive"))
      (node (ref "U3") (pin "18") (pinfunction "DV/DT_18") (pintype "bidirectional"))
    )
    (net (code "103") (name "Net-(U3-EN{slash}UVLO)") (class "Default")
      (node (ref "R13") (pin "1") (pinfunction "1_1") (pintype "passive"))
      (node (ref "R9") (pin "2") (pinfunction "2_2") (pintype "passive"))
      (node (ref "U3") (pin "14") (pinfunction "EN/UVLO_14") (pintype "bidirectional"))
    )
    (net (code "104") (name "Net-(U3-ILIM)") (class "Default")
      (node (ref "RILIM2") (pin "1") (pinfunction "1_1") (pintype "passive"))
      (node (ref "U3") (pin "17") (pinfunction "ILIM_17") (pintype "bidirectional"))
    )
    (net (code "105") (name "Net-(U3-PGOOD)") (class "Default")
      (node (ref "TP1GOOD") (pin "1") (pinfunction "1_1") (pintype "passive"))
      (node (ref "U3") (pin "2") (pinfunction "PGOOD_2") (pintype "bidirectional"))
    )
    (net (code "106") (name "Net-(U4-DV{slash}DT)") (class "Default")
      (node (ref "C11") (pin "1") (pinfunction "1_1") (pintype "passive"))
      (node (ref "U4") (pin "18") (pinfunction "DV/DT_18") (pintype "bidirectional"))
    )
    (net (code "107") (name "Net-(U4-EN{slash}UVLO)") (class "Default")
      (node (ref "R20") (pin "2") (pinfunction "2_2") (pintype "passive"))
      (node (ref "R24") (pin "1") (pinfunction "1_1") (pintype "passive"))
      (node (ref "U4") (pin "14") (pinfunction "EN/UVLO_14") (pintype "bidirectional"))
    )
    (net (code "108") (name "Net-(U4-ILIM)") (class "Default")
      (node (ref "RILIM3") (pin "1") (pinfunction "1_1") (pintype "passive"))
      (node (ref "U4") (pin "17") (pinfunction "ILIM_17") (pintype "bidirectional"))
    )
    (net (code "109") (name "Net-(U4-PGOOD)") (class "Default")
      (node (ref "TP2GOOD") (pin "1") (pinfunction "1_1") (pintype "passive"))
      (node (ref "U4") (pin "2") (pinfunction "PGOOD_2") (pintype "bidirectional"))
    )
    (net (code "110") (name "Net-(U5-DV{slash}DT)") (class "Default")
      (node (ref "C16") (pin "1") (pinfunction "1_1") (pintype "passive"))
      (node (ref "U5") (pin "18") (pinfunction "DV/DT_18") (pintype "bidirectional"))
    )
    (net (code "111") (name "Net-(U5-EN{slash}UVLO)") (class "Default")
      (node (ref "R27") (pin "2") (pinfunction "2_2") (pintype "passive"))
      (node (ref "R31") (pin "1") (pinfunction "1_1") (pintype "passive"))
      (node (ref "U5") (pin "14") (pinfunction "EN/UVLO_14") (pintype "bidirectional"))
    )
    (net (code "112") (name "Net-(U5-ILIM)") (class "Default")
      (node (ref "RILIM4") (pin "1") (pinfunction "1_1") (pintype "passive"))
      (node (ref "U5") (pin "17") (pinfunction "ILIM_17") (pintype "bidirectional"))
    )
    (net (code "113") (name "Net-(U5-PGOOD)") (class "Default")
      (node (ref "TP3GOOD") (pin "1") (pinfunction "1_1") (pintype "passive"))
      (node (ref "U5") (pin "2") (pinfunction "PGOOD_2") (pintype "bidirectional"))
    )
    (net (code "114") (name "Net-(U6-DV{slash}DT)") (class "Default")
      (node (ref "C21") (pin "1") (pinfunction "1_1") (pintype "passive"))
      (node (ref "U6") (pin "18") (pinfunction "DV/DT_18") (pintype "bidirectional"))
    )
    (net (code "115") (name "Net-(U6-EN{slash}UVLO)") (class "Default")
      (node (ref "R41") (pin "2") (pinfunction "2_2") (pintype "passive"))
      (node (ref "R45") (pin "1") (pinfunction "1_1") (pintype "passive"))
      (node (ref "U6") (pin "14") (pinfunction "EN/UVLO_14") (pintype "bidirectional"))
    )
    (net (code "116") (name "Net-(U6-ILIM)") (class "Default")
      (node (ref "RILIM5") (pin "1") (pinfunction "1_1") (pintype "passive"))
      (node (ref "U6") (pin "17") (pinfunction "ILIM_17") (pintype "bidirectional"))
    )
    (net (code "117") (name "Net-(U6-PGOOD)") (class "Default")
      (node (ref "TP4GOOD") (pin "1") (pinfunction "1_1") (pintype "passive"))
      (node (ref "U6") (pin "2") (pinfunction "PGOOD_2") (pintype "bidirectional"))
    )
    (net (code "118") (name "Net-(U7-(IC1)PD4)") (class "Default")
      (node (ref "U7") (pin "29") (pinfunction "(IC1)PD4_29") (pintype "bidirectional"))
      (node (ref "U8") (pin "7") (pinfunction "ADDC_7") (pintype "bidirectional"))
    )
    (net (code "119") (name "Net-(U7-(IC3{slash}INT7)PE7)") (class "Default")
      (node (ref "TP50") (pin "1") (pinfunction "1_1") (pintype "passive"))
      (node (ref "U7") (pin "9") (pinfunction "(IC3/INT7)PE7_9") (pintype "bidirectional"))
    )
    (net (code "120") (name "Net-(U7-(MISO)PB3)") (class "Default")
      (node (ref "TP15") (pin "1") (pinfunction "1_1") (pintype "passive"))
      (node (ref "U7") (pin "13") (pinfunction "(MISO)PB3_13") (pintype "bidirectional"))
    )
    (net (code "121") (name "Net-(U7-(MOSI)PB2)") (class "Default")
      (node (ref "TP9") (pin "1") (pinfunction "1_1") (pintype "passive"))
      (node (ref "U7") (pin "12") (pinfunction "(MOSI)PB2_12") (pintype "bidirectional"))
    )
    (net (code "122") (name "Net-(U7-(OC0)PB4)") (class "Default")
      (node (ref "TP16") (pin "1") (pinfunction "1_1") (pintype "passive"))
      (node (ref "U7") (pin "14") (pinfunction "(OC0)PB4_14") (pintype "bidirectional"))
    )
    (net (code "123") (name "Net-(U7-(OC1A)PB5)") (class "Default")
      (node (ref "TP17") (pin "1") (pinfunction "1_1") (pintype "passive"))
      (node (ref "U7") (pin "15") (pinfunction "(OC1A)PB5_15") (pintype "bidirectional"))
    )
    (net (code "124") (name "Net-(U7-(OC1B)PB6)") (class "Default")
      (node (ref "TP18") (pin "1") (pinfunction "1_1") (pintype "passive"))
      (node (ref "U7") (pin "16") (pinfunction "(OC1B)PB6_16") (pintype "bidirectional"))
    )
    (net (code "125") (name "Net-(U7-(OC2{slash}OC1C)PB7)") (class "Default")
      (node (ref "TP19") (pin "1") (pinfunction "1_1") (pintype "passive"))
      (node (ref "U7") (pin "17") (pinfunction "(OC2/OC1C)PB7_17") (pintype "bidirectional"))
    )
    (net (code "126") (name "Net-(U7-(OC3A{slash}AIN1)PE3)") (class "Default")
      (node (ref "TP54") (pin "1") (pinfunction "1_1") (pintype "passive"))
      (node (ref "U7") (pin "5") (pinfunction "(OC3A/AIN1)PE3_5") (pintype "bidirectional"))
    )
    (net (code "127") (name "Net-(U7-(OC3B{slash}INT4)PE4)") (class "Default")
      (node (ref "TP53") (pin "1") (pinfunction "1_1") (pintype "passive"))
      (node (ref "U7") (pin "6") (pinfunction "(OC3B/INT4)PE4_6") (pintype "bidirectional"))
    )
    (net (code "128") (name "Net-(U7-(OC3C{slash}INT5)PE5)") (class "Default")
      (node (ref "TP52") (pin "1") (pinfunction "1_1") (pintype "passive"))
      (node (ref "U7") (pin "7") (pinfunction "(OC3C/INT5)PE5_7") (pintype "bidirectional"))
    )
    (net (code "129") (name "Net-(U7-(SCK)PB1)") (class "Default")
      (node (ref "TP8") (pin "1") (pinfunction "1_1") (pintype "passive"))
      (node (ref "U7") (pin "11") (pinfunction "(SCK)PB1_11") (pintype "bidirectional"))
    )
    (net (code "130") (name "Net-(U7-(SS)PB0)") (class "Default")
      (node (ref "TP7") (pin "1") (pinfunction "1_1") (pintype "passive"))
      (node (ref "U7") (pin "10") (pinfunction "(SS)PB0_10") (pintype "bidirectional"))
    )
    (net (code "131") (name "Net-(U7-(T1)PD6)") (class "Default")
      (node (ref "U7") (pin "31") (pinfunction "(T1)PD6_31") (pintype "bidirectional"))
      (node (ref "U8") (pin "9") (pinfunction "ADDA_9") (pintype "bidirectional"))
    )
    (net (code "132") (name "Net-(U7-(T2)PD7)") (class "Default")
      (node (ref "TP56") (pin "1") (pinfunction "1_1") (pintype "passive"))
      (node (ref "U7") (pin "32") (pinfunction "(T2)PD7_32") (pintype "bidirectional"))
    )
    (net (code "133") (name "Net-(U7-(T3{slash}INT6)PE6)") (class "Default")
      (node (ref "TP51") (pin "1") (pinfunction "1_1") (pintype "passive"))
      (node (ref "U7") (pin "8") (pinfunction "(T3/INT6)PE6_8") (pintype "bidirectional"))
    )
    (net (code "134") (name "Net-(U7-(XCK0{slash}AIN0)PE2)") (class "Default")
      (node (ref "TP55") (pin "1") (pinfunction "1_1") (pintype "passive"))
      (node (ref "U7") (pin "4") (pinfunction "(XCK0/AIN0)PE2_4") (pintype "bidirectional"))
    )
    (net (code "135") (name "Net-(U7-(XCK1)PD5)") (class "Default")
      (node (ref "U7") (pin "30") (pinfunction "(XCK1)PD5_30") (pintype "bidirectional"))
      (node (ref "U8") (pin "8") (pinfunction "ADDB_8") (pintype "bidirectional"))
    )
    (net (code "136") (name "Net-(U7-AREF)") (class "Default")
      (node (ref "C19") (pin "2") (pinfunction "2_2") (pintype "passive"))
      (node (ref "U7") (pin "62") (pinfunction "AREF_62") (pintype "passive"))
    )
    (net (code "137") (name "Net-(U7-PEN)") (class "Default")
      (node (ref "TP4") (pin "1") (pinfunction "1_1") (pintype "passive"))
      (node (ref "U7") (pin "1") (pinfunction "PEN_1") (pintype "input"))
    )
    (net (code "138") (name "Net-(U7-PF0(ADC0))") (class "Default")
      (node (ref "U7") (pin "61") (pinfunction "PF0(ADC0)_61") (pintype "bidirectional"))
      (node (ref "U8") (pin "1") (pinfunction "COMM_1") (pintype "bidirectional"))
    )
    (net (code "139") (name "Net-(U7-PF1(ADC1))") (class "Default")
      (node (ref "TP48") (pin "1") (pinfunction "1_1") (pintype "passive"))
      (node (ref "U7") (pin "60") (pinfunction "PF1(ADC1)_60") (pintype "bidirectional"))
    )
    (net (code "140") (name "Net-(U7-PF2(ADC2))") (class "Default")
      (node (ref "TP49") (pin "1") (pinfunction "1_1") (pintype "passive"))
      (node (ref "U7") (pin "59") (pinfunction "PF2(ADC2)_59") (pintype "bidirectional"))
    )
    (net (code "141") (name "Net-(U7-PF3(ADC3))") (class "Default")
      (node (ref "TP47") (pin "1") (pinfunction "1_1") (pintype "passive"))
      (node (ref "U7") (pin "58") (pinfunction "PF3(ADC3)_58") (pintype "bidirectional"))
    )
    (net (code "142") (name "Net-(U7-PG3(TOSC2))") (class "Default")
      (node (ref "TP46") (pin "1") (pinfunction "1_1") (pintype "passive"))
      (node (ref "U7") (pin "18") (pinfunction "PG3(TOSC2)_18") (pintype "bidirectional"))
    )
    (net (code "143") (name "Net-(U7-PG4(TOSC1))") (class "Default")
      (node (ref "TP27") (pin "1") (pinfunction "1_1") (pintype "passive"))
      (node (ref "U7") (pin "19") (pinfunction "PG4(TOSC1)_19") (pintype "bidirectional"))
    )
    (net (code "144") (name "Net-(U7-XTAL1)") (class "Default")
      (node (ref "C17") (pin "2") (pinfunction "2_2") (pintype "passive"))
      (node (ref "U7") (pin "24") (pinfunction "XTAL1_24") (pintype "passive"))
      (node (ref "X1") (pin "P$2") (pinfunction "P$2_P$2") (pintype "bidirectional"))
    )
    (net (code "145") (name "Net-(U7-XTAL2)") (class "Default")
      (node (ref "C15") (pin "2") (pinfunction "2_2") (pintype "passive"))
      (node (ref "U7") (pin "23") (pinfunction "XTAL2_23") (pintype "passive"))
      (node (ref "X1") (pin "P$1") (pinfunction "P$1_P$1") (pintype "bidirectional"))
    )
    (net (code "146") (name "Net-(U9-DV{slash}DT)") (class "Default")
      (node (ref "C24") (pin "1") (pinfunction "1_1") (pintype "passive"))
      (node (ref "U9") (pin "18") (pinfunction "DV/DT_18") (pintype "bidirectional"))
    )
    (net (code "147") (name "Net-(U9-EN{slash}UVLO)") (class "Default")
      (node (ref "R47") (pin "2") (pinfunction "2_2") (pintype "passive"))
      (node (ref "R51") (pin "1") (pinfunction "1_1") (pintype "passive"))
      (node (ref "U9") (pin "14") (pinfunction "EN/UVLO_14") (pintype "bidirectional"))
    )
    (net (code "148") (name "Net-(U9-ILIM)") (class "Default")
      (node (ref "RILIM6") (pin "1") (pinfunction "1_1") (pintype "passive"))
      (node (ref "U9") (pin "17") (pinfunction "ILIM_17") (pintype "bidirectional"))
    )
    (net (code "149") (name "Net-(U9-PGOOD)") (class "Default")
      (node (ref "TP5GOOD") (pin "1") (pinfunction "1_1") (pintype "passive"))
      (node (ref "U9") (pin "2") (pinfunction "PGOOD_2") (pintype "bidirectional"))
    )
    (net (code "150") (name "Net-(U10-DV{slash}DT)") (class "Default")
      (node (ref "C26") (pin "1") (pinfunction "1_1") (pintype "passive"))
      (node (ref "U10") (pin "18") (pinfunction "DV/DT_18") (pintype "bidirectional"))
    )
    (net (code "151") (name "Net-(U10-EN{slash}UVLO)") (class "Default")
      (node (ref "R55") (pin "2") (pinfunction "2_2") (pintype "passive"))
      (node (ref "R59") (pin "1") (pinfunction "1_1") (pintype "passive"))
      (node (ref "U10") (pin "14") (pinfunction "EN/UVLO_14") (pintype "bidirectional"))
    )
    (net (code "152") (name "Net-(U10-ILIM)") (class "Default")
      (node (ref "RILIM7") (pin "1") (pinfunction "1_1") (pintype "passive"))
      (node (ref "U10") (pin "17") (pinfunction "ILIM_17") (pintype "bidirectional"))
    )
    (net (code "153") (name "Net-(U10-PGOOD)") (class "Default")
      (node (ref "TP6GOOD") (pin "1") (pinfunction "1_1") (pintype "passive"))
      (node (ref "U10") (pin "2") (pinfunction "PGOOD_2") (pintype "bidirectional"))
    )
    (net (code "154") (name "Net-(U13-DV{slash}DT)") (class "Default")
      (node (ref "C30") (pin "1") (pinfunction "1_1") (pintype "passive"))
      (node (ref "U13") (pin "18") (pinfunction "DV/DT_18") (pintype "bidirectional"))
    )
    (net (code "155") (name "Net-(U13-EN{slash}UVLO)") (class "Default")
      (node (ref "R65") (pin "2") (pinfunction "2_2") (pintype "passive"))
      (node (ref "R69") (pin "1") (pinfunction "1_1") (pintype "passive"))
      (node (ref "U13") (pin "14") (pinfunction "EN/UVLO_14") (pintype "bidirectional"))
    )
    (net (code "156") (name "Net-(U13-ILIM)") (class "Default")
      (node (ref "RILIM8") (pin "1") (pinfunction "1_1") (pintype "passive"))
      (node (ref "U13") (pin "17") (pinfunction "ILIM_17") (pintype "bidirectional"))
    )
    (net (code "157") (name "Net-(U13-PGOOD)") (class "Default")
      (node (ref "TP7GOOD") (pin "1") (pinfunction "1_1") (pintype "passive"))
      (node (ref "U13") (pin "2") (pinfunction "PGOOD_2") (pintype "bidirectional"))
    )
    (net (code "158") (name "V+") (class "Default")
      (node (ref "C3") (pin "+") (pinfunction "+_+") (pintype "passive"))
      (node (ref "C6") (pin "2") (pinfunction "2_2") (pintype "passive"))
      (node (ref "D1") (pin "2") (pinfunction "-_2") (pintype "passive"))
      (node (ref "D2") (pin "2") (pinfunction "-_2") (pintype "passive"))
      (node (ref "R7") (pin "1") (pinfunction "1_1") (pintype "passive"))
      (node (ref "U2") (pin "1") (pinfunction "VIN_1") (pintype "bidirectional"))
    )
    (net (code "159") (name "VBUS") (class "Default")
      (node (ref "C1") (pin "2") (pinfunction "2_2") (pintype "passive"))
      (node (ref "C14") (pin "2") (pinfunction "2_2") (pintype "passive"))
      (node (ref "C20") (pin "2") (pinfunction "2_2") (pintype "passive"))
      (node (ref "C22") (pin "2") (pinfunction "2_2") (pintype "passive"))
      (node (ref "C25") (pin "2") (pinfunction "2_2") (pintype "passive"))
      (node (ref "C29") (pin "2") (pinfunction "2_2") (pintype "passive"))
      (node (ref "C7") (pin "2") (pinfunction "2_2") (pintype "passive"))
      (node (ref "C9") (pin "2") (pinfunction "2_2") (pintype "passive"))
      (node (ref "CF1") (pin "P$1") (pinfunction "1_P$1") (pintype "passive"))
      (node (ref "CF1") (pin "P$2") (pinfunction "2_P$2") (pintype "passive"))
      (node (ref "CF1") (pin "P$3") (pinfunction "3_P$3") (pintype "passive"))
      (node (ref "CF1") (pin "P$4") (pinfunction "4_P$4") (pintype "passive"))
      (node (ref "CF1") (pin "P$5") (pinfunction "5_P$5") (pintype "passive"))
      (node (ref "CF1") (pin "P$6") (pinfunction "6_P$6") (pintype "passive"))
      (node (ref "CF1") (pin "P$7") (pinfunction "7_P$7") (pintype "passive"))
      (node (ref "CF1") (pin "P$8") (pinfunction "8_P$8") (pintype "passive"))
      (node (ref "D1") (pin "1") (pinfunction "+_1") (pintype "passive"))
      (node (ref "Q1") (pin "2") (pinfunction "S_2") (pintype "passive"))
      (node (ref "Q10") (pin "2") (pinfunction "S_2") (pintype "passive"))
      (node (ref "Q2") (pin "2") (pinfunction "S_2") (pintype "passive"))
      (node (ref "Q4") (pin "2") (pinfunction "S_2") (pintype "passive"))
      (node (ref "Q5") (pin "2") (pinfunction "S_2") (pintype "passive"))
      (node (ref "Q6") (pin "2") (pinfunction "S_2") (pintype "passive"))
      (node (ref "Q7") (pin "2") (pinfunction "S_2") (pintype "passive"))
      (node (ref "Q8") (pin "2") (pinfunction "S_2") (pintype "passive"))
      (node (ref "R1") (pin "1") (pinfunction "1_1") (pintype "passive"))
      (node (ref "R17") (pin "1") (pinfunction "1_1") (pintype "passive"))
      (node (ref "R26") (pin "1") (pinfunction "1_1") (pintype "passive"))
      (node (ref "R40") (pin "1") (pinfunction "1_1") (pintype "passive"))
      (node (ref "R46") (pin "1") (pinfunction "1_1") (pintype "passive"))
      (node (ref "R53") (pin "1") (pinfunction "1_1") (pintype "passive"))
      (node (ref "R64") (pin "1") (pinfunction "1_1") (pintype "passive"))
      (node (ref "R8") (pin "1") (pinfunction "1_1") (pintype "passive"))
      (node (ref "U1") (pin "10") (pinfunction "IN_10") (pintype "bidirectional"))
      (node (ref "U1") (pin "11") (pinfunction "IN_11") (pintype "bidirectional"))
      (node (ref "U1") (pin "12") (pinfunction "IN_12") (pintype "bidirectional"))
      (node (ref "U1") (pin "13") (pinfunction "IN_13") (pintype "bidirectional"))
      (node (ref "U1") (pin "9") (pinfunction "IN_9") (pintype "bidirectional"))
      (node (ref "U10") (pin "10") (pinfunction "IN_10") (pintype "bidirectional"))
      (node (ref "U10") (pin "11") (pinfunction "IN_11") (pintype "bidirectional"))
      (node (ref "U10") (pin "12") (pinfunction "IN_12") (pintype "bidirectional"))
      (node (ref "U10") (pin "13") (pinfunction "IN_13") (pintype "bidirectional"))
      (node (ref "U10") (pin "9") (pinfunction "IN_9") (pintype "bidirectional"))
      (node (ref "U13") (pin "10") (pinfunction "IN_10") (pintype "bidirectional"))
      (node (ref "U13") (pin "11") (pinfunction "IN_11") (pintype "bidirectional"))
      (node (ref "U13") (pin "12") (pinfunction "IN_12") (pintype "bidirectional"))
      (node (ref "U13") (pin "13") (pinfunction "IN_13") (pintype "bidirectional"))
      (node (ref "U13") (pin "9") (pinfunction "IN_9") (pintype "bidirectional"))
      (node (ref "U3") (pin "10") (pinfunction "IN_10") (pintype "bidirectional"))
      (node (ref "U3") (pin "11") (pinfunction "IN_11") (pintype "bidirectional"))
      (node (ref "U3") (pin "12") (pinfunction "IN_12") (pintype "bidirectional"))
      (node (ref "U3") (pin "13") (pinfunction "IN_13") (pintype "bidirectional"))
      (node (ref "U3") (pin "9") (pinfunction "IN_9") (pintype "bidirectional"))
      (node (ref "U4") (pin "10") (pinfunction "IN_10") (pintype "bidirectional"))
      (node (ref "U4") (pin "11") (pinfunction "IN_11") (pintype "bidirectional"))
      (node (ref "U4") (pin "12") (pinfunction "IN_12") (pintype "bidirectional"))
      (node (ref "U4") (pin "13") (pinfunction "IN_13") (pintype "bidirectional"))
      (node (ref "U4") (pin "9") (pinfunction "IN_9") (pintype "bidirectional"))
      (node (ref "U5") (pin "10") (pinfunction "IN_10") (pintype "bidirectional"))
      (node (ref "U5") (pin "11") (pinfunction "IN_11") (pintype "bidirectional"))
      (node (ref "U5") (pin "12") (pinfunction "IN_12") (pintype "bidirectional"))
      (node (ref "U5") (pin "13") (pinfunction "IN_13") (pintype "bidirectional"))
      (node (ref "U5") (pin "9") (pinfunction "IN_9") (pintype "bidirectional"))
      (node (ref "U6") (pin "10") (pinfunction "IN_10") (pintype "bidirectional"))
      (node (ref "U6") (pin "11") (pinfunction "IN_11") (pintype "bidirectional"))
      (node (ref "U6") (pin "12") (pinfunction "IN_12") (pintype "bidirectional"))
      (node (ref "U6") (pin "13") (pinfunction "IN_13") (pintype "bidirectional"))
      (node (ref "U6") (pin "9") (pinfunction "IN_9") (pintype "bidirectional"))
      (node (ref "U9") (pin "10") (pinfunction "IN_10") (pintype "bidirectional"))
      (node (ref "U9") (pin "11") (pinfunction "IN_11") (pintype "bidirectional"))
      (node (ref "U9") (pin "12") (pinfunction "IN_12") (pintype "bidirectional"))
      (node (ref "U9") (pin "13") (pinfunction "IN_13") (pintype "bidirectional"))
      (node (ref "U9") (pin "9") (pinfunction "IN_9") (pintype "bidirectional"))
    )
    (net (code "160") (name "VCB0_IMON") (class "Default")
      (node (ref "RIMON1") (pin "1") (pinfunction "1_1") (pintype "passive"))
      (node (ref "U1") (pin "19") (pinfunction "IMON_19") (pintype "bidirectional"))
      (node (ref "U8") (pin "11") (pinfunction "NO0\\_11") (pintype "bidirectional"))
    )
    (net (code "161") (name "VCB1_IMON") (class "Default")
      (node (ref "RIMON2") (pin "1") (pinfunction "1_1") (pintype "passive"))
      (node (ref "U3") (pin "19") (pinfunction "IMON_19") (pintype "bidirectional"))
      (node (ref "U8") (pin "12") (pinfunction "NO1_12") (pintype "bidirectional"))
    )
    (net (code "162") (name "VCB2_IMON") (class "Default")
      (node (ref "RIMON3") (pin "1") (pinfunction "1_1") (pintype "passive"))
      (node (ref "U4") (pin "19") (pinfunction "IMON_19") (pintype "bidirectional"))
      (node (ref "U8") (pin "13") (pinfunction "NO2_13") (pintype "bidirectional"))
    )
    (net (code "163") (name "VCB3_IMON") (class "Default")
      (node (ref "RIMON4") (pin "1") (pinfunction "1_1") (pintype "passive"))
      (node (ref "U5") (pin "19") (pinfunction "IMON_19") (pintype "bidirectional"))
      (node (ref "U8") (pin "10") (pinfunction "NO3_10") (pintype "bidirectional"))
    )
    (net (code "164") (name "VCB4_IMON") (class "Default")
      (node (ref "RIMON5") (pin "1") (pinfunction "1_1") (pintype "passive"))
      (node (ref "U6") (pin "19") (pinfunction "IMON_19") (pintype "bidirectional"))
      (node (ref "U8") (pin "15") (pinfunction "NO4_15") (pintype "bidirectional"))
    )
    (net (code "165") (name "VCB5_IMON") (class "Default")
      (node (ref "RIMON6") (pin "1") (pinfunction "1_1") (pintype "passive"))
      (node (ref "U8") (pin "3") (pinfunction "NO5_3") (pintype "bidirectional"))
      (node (ref "U9") (pin "19") (pinfunction "IMON_19") (pintype "bidirectional"))
    )
    (net (code "166") (name "VCB6_IMON") (class "Default")
      (node (ref "RIMON7") (pin "1") (pinfunction "1_1") (pintype "passive"))
      (node (ref "U10") (pin "19") (pinfunction "IMON_19") (pintype "bidirectional"))
      (node (ref "U8") (pin "16") (pinfunction "NO6_16") (pintype "bidirectional"))
    )
    (net (code "167") (name "VCB7_IMON") (class "Default")
      (node (ref "RIMON8") (pin "1") (pinfunction "1_1") (pintype "passive"))
      (node (ref "U13") (pin "19") (pinfunction "IMON_19") (pintype "bidirectional"))
      (node (ref "U8") (pin "2") (pinfunction "NO7_2") (pintype "bidirectional"))
    )
    (net (code "168") (name "VSOL") (class "Default")
      (node (ref "CF1") (pin "P$10") (pinfunction "10_P$10") (pintype "passive"))
      (node (ref "CF1") (pin "P$11") (pinfunction "11_P$11") (pintype "passive"))
      (node (ref "CF1") (pin "P$12") (pinfunction "12_P$12") (pintype "passive"))
      (node (ref "CF1") (pin "P$13") (pinfunction "13_P$13") (pintype "passive"))
      (node (ref "CF1") (pin "P$14") (pinfunction "14_P$14") (pintype "passive"))
      (node (ref "CF1") (pin "P$9") (pinfunction "9_P$9") (pintype "passive"))
      (node (ref "D2") (pin "1") (pinfunction "+_1") (pintype "passive"))
    )
    (net (code "169") (name "unconnected-(J1-RTCK-Pad7)") (class "Default")
      (node (ref "J1") (pin "7") (pinfunction "RTCK_7") (pintype "passive"))
    )
    (net (code "170") (name "unconnected-(U2-BYP-Pad4)") (class "Default")
      (node (ref "U2") (pin "4") (pinfunction "BYP_4") (pintype "bidirectional"))
    )
    (net (code "171") (name "unconnected-(U8-NC-Pad5)") (class "Default")
      (node (ref "U8") (pin "5") (pinfunction "NC_5") (pintype "bidirectional"))
    )
  )
)
